# design.net
KiCad netlist of a schematic drawn in EasyEDA Pro
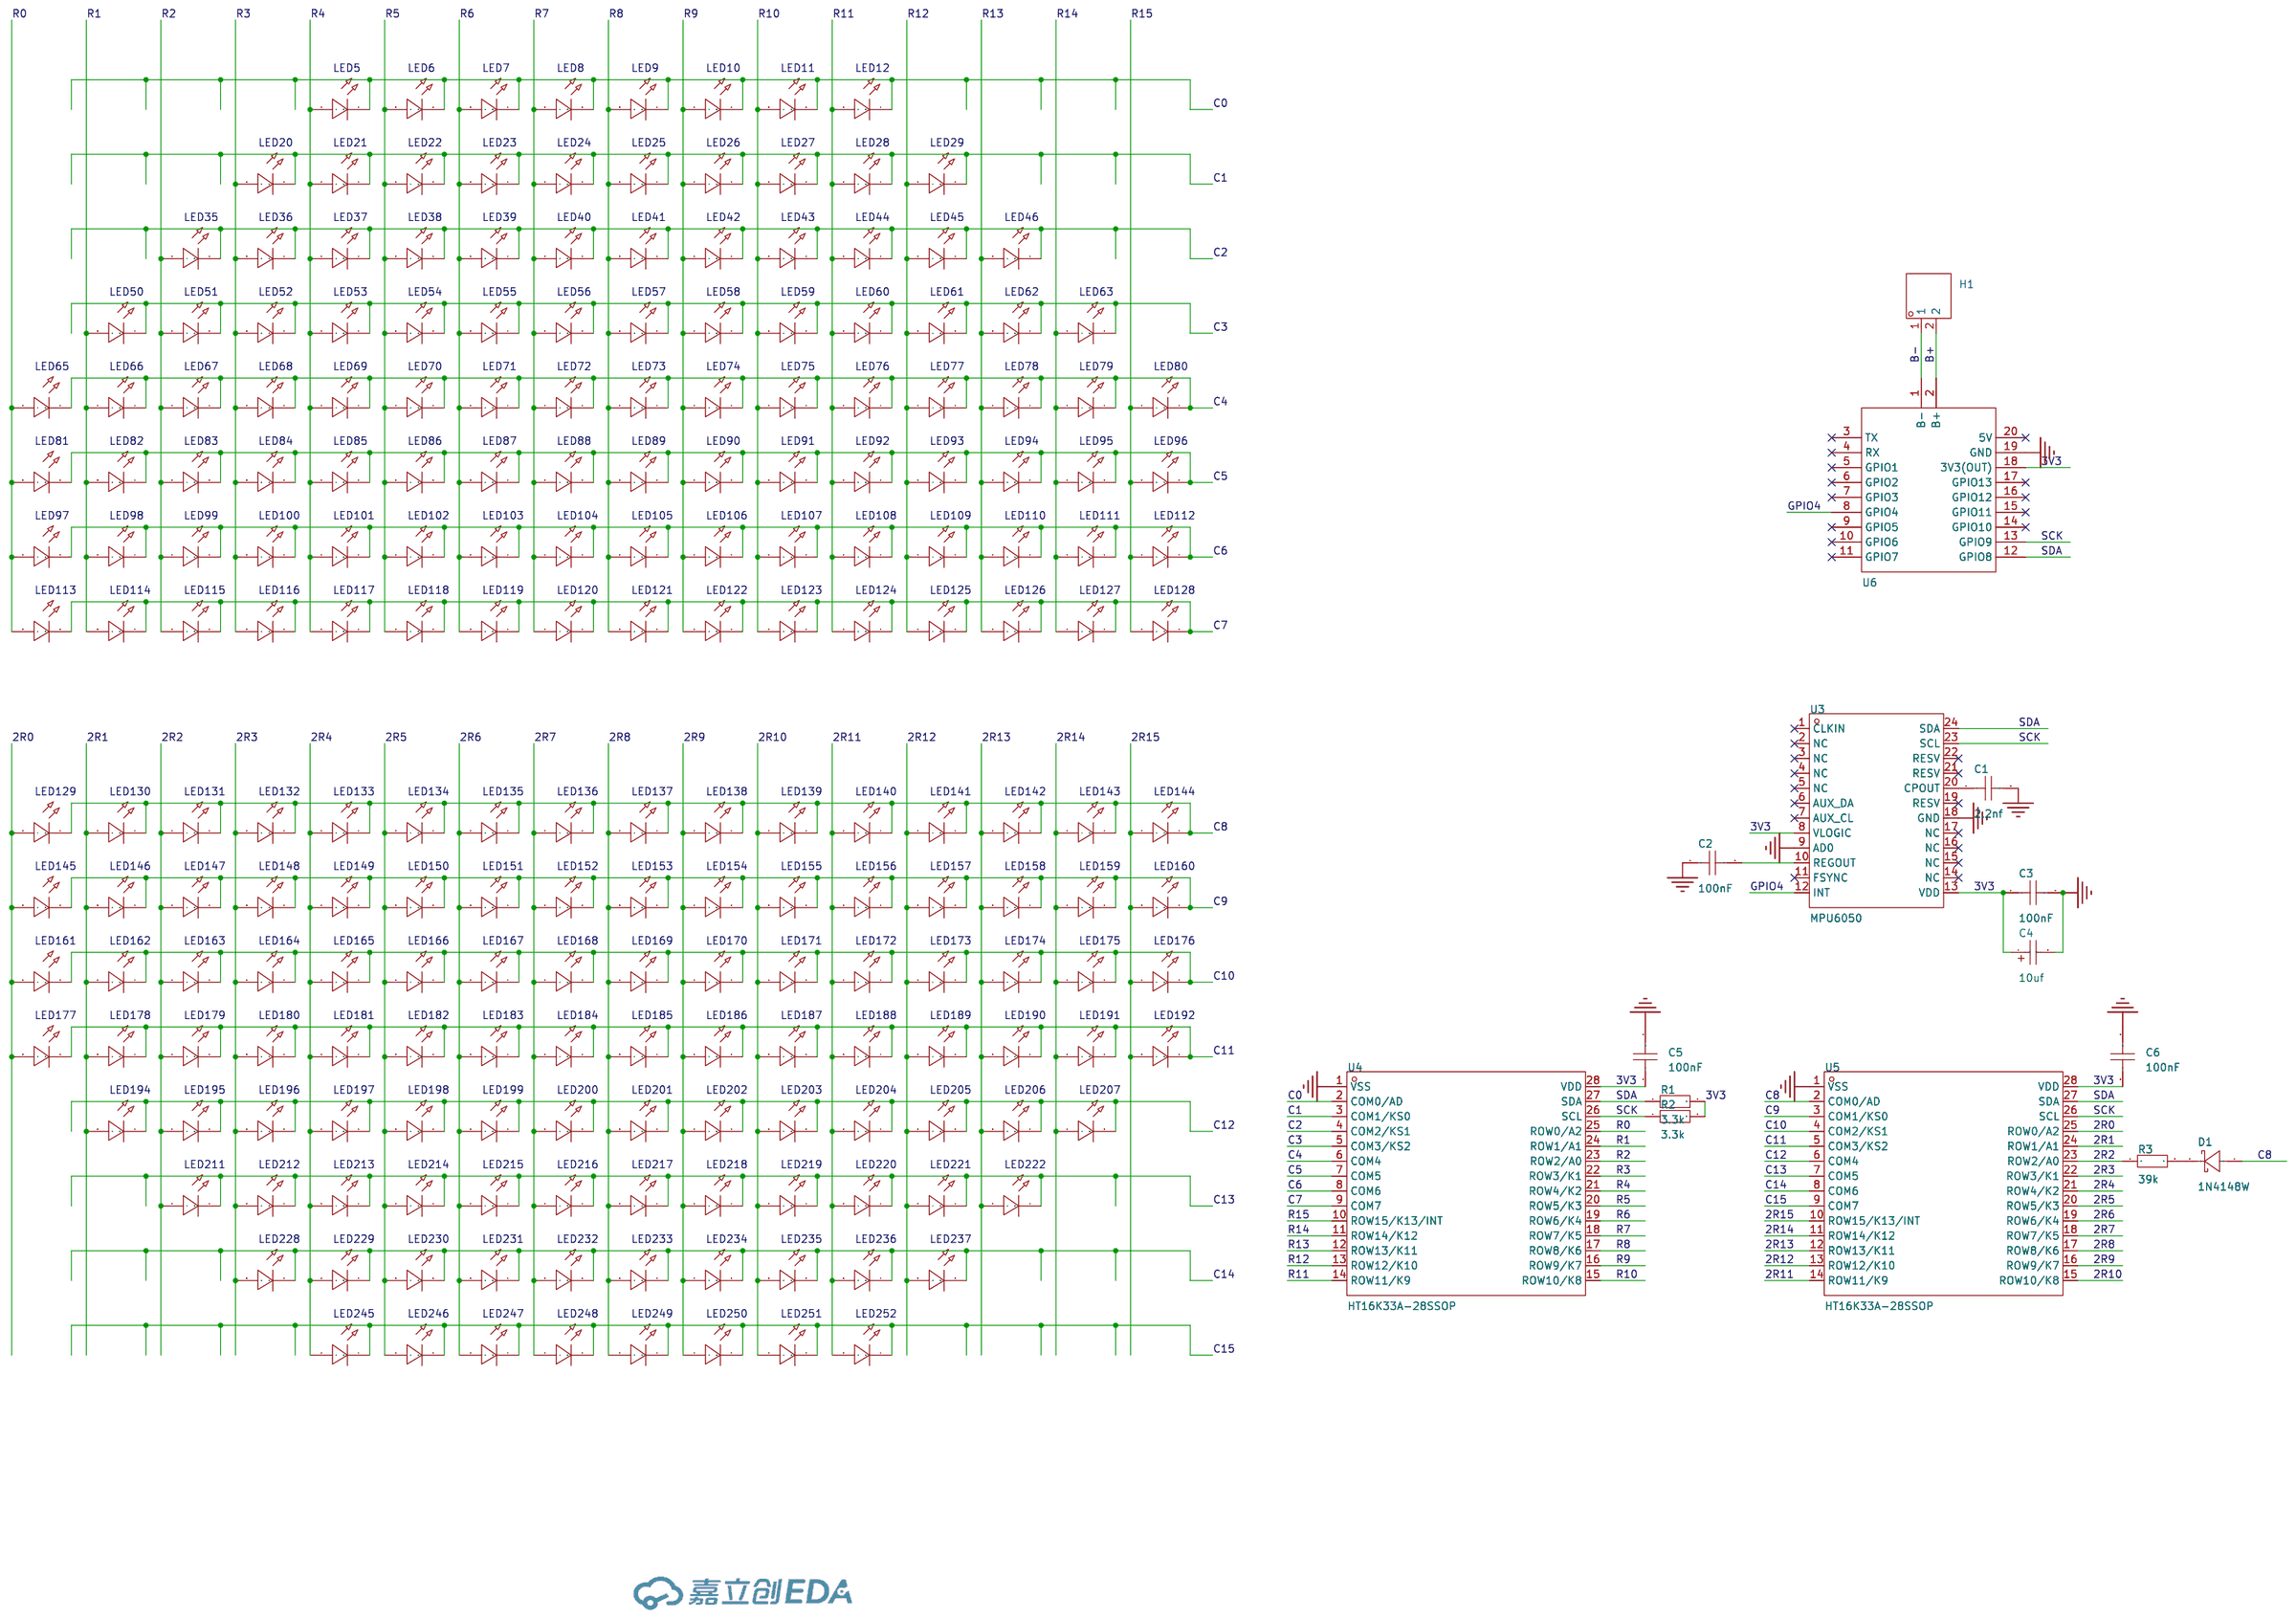
[diagram p0: schematic sheet]

(export (version "E")
  (design (tool "Eeschema 10.0.6"))
  (components
    (comp (ref "C1")
      (value "2.2nf")
      (footprint "easyedapro:C0603")
      (libsource (lib "easyedapro") (part "CapAcitance"))
    )
    (comp (ref "C2")
      (value "100nF")
      (footprint "easyedapro:C0603")
      (libsource (lib "easyedapro") (part "CapAcitance"))
    )
    (comp (ref "C3")
      (value "100nF")
      (footprint "easyedapro:C0603")
      (libsource (lib "easyedapro") (part "CapAcitance"))
    )
    (comp (ref "C4")
      (value "10uf")
      (footprint "easyedapro:CASE-B_3528")
      (description "容值:100uF;精度:±10%;额定电压:6.3V;等效串联电阻(ESR):1.7Ω@100kHz;")
      (fields (field (name "Manufacturer Part") "TAJB107K006RNJ") (field (name "Manufacturer") "Kyocera AVX"))
      (libsource (lib "easyedapro") (part "TAJB107K006RNJ"))
    )
    (comp (ref "C5")
      (value "100nF")
      (footprint "easyedapro:C0603")
      (libsource (lib "easyedapro") (part "CapAcitance"))
    )
    (comp (ref "C6")
      (value "100nF")
      (footprint "easyedapro:C0603")
      (libsource (lib "easyedapro") (part "CapAcitance"))
    )
    (comp (ref "D1")
      (value "1N4148W")
      (footprint "easyedapro:SOD-123_L2.7-W1.6-LS3.7-FD")
      (description "二极管配置:独立式;正向压降(Vf):1.25V@150mA;直流反向耐压(Vr):100V;整流电流:150mA;反向恢复时间(Trr):4ns;")
      (fields (field (name "Manufacturer") "R+O(宏嘉诚)"))
      (libsource (lib "easyedapro") (part "1N4148W_C7420318"))
    )
    (comp (ref "H1")
      (value "~")
      (footprint "easyedapro:HDR-TH_2P-P2.54-V-M-1")
      (libsource (lib "easyedapro") (part "210S-1*2P L=11.6MMGold-plated black"))
    )
    (comp (ref "LED5")
      (value "~")
      (footprint "easyedapro:LED_0402")
      (libsource (lib "easyedapro") (part "LED_G"))
    )
    (comp (ref "LED6")
      (value "~")
      (footprint "easyedapro:LED_0402")
      (libsource (lib "easyedapro") (part "LED_G"))
    )
    (comp (ref "LED7")
      (value "~")
      (footprint "easyedapro:LED_0402")
      (libsource (lib "easyedapro") (part "LED_G"))
    )
    (comp (ref "LED8")
      (value "~")
      (footprint "easyedapro:LED_0402")
      (libsource (lib "easyedapro") (part "LED_G"))
    )
    (comp (ref "LED9")
      (value "~")
      (footprint "easyedapro:LED_0402")
      (libsource (lib "easyedapro") (part "LED_G"))
    )
    (comp (ref "LED10")
      (value "~")
      (footprint "easyedapro:LED_0402")
      (libsource (lib "easyedapro") (part "LED_G"))
    )
    (comp (ref "LED11")
      (value "~")
      (footprint "easyedapro:LED_0402")
      (libsource (lib "easyedapro") (part "LED_G"))
    )
    (comp (ref "LED12")
      (value "~")
      (footprint "easyedapro:LED_0402")
      (libsource (lib "easyedapro") (part "LED_G"))
    )
    (comp (ref "LED20")
      (value "~")
      (footprint "easyedapro:LED_0402")
      (libsource (lib "easyedapro") (part "LED_G"))
    )
    (comp (ref "LED21")
      (value "~")
      (footprint "easyedapro:LED_0402")
      (libsource (lib "easyedapro") (part "LED_G"))
    )
    (comp (ref "LED22")
      (value "~")
      (footprint "easyedapro:LED_0402")
      (libsource (lib "easyedapro") (part "LED_G"))
    )
    (comp (ref "LED23")
      (value "~")
      (footprint "easyedapro:LED_0402")
      (libsource (lib "easyedapro") (part "LED_G"))
    )
    (comp (ref "LED24")
      (value "~")
      (footprint "easyedapro:LED_0402")
      (libsource (lib "easyedapro") (part "LED_G"))
    )
    (comp (ref "LED25")
      (value "~")
      (footprint "easyedapro:LED_0402")
      (libsource (lib "easyedapro") (part "LED_G"))
    )
    (comp (ref "LED26")
      (value "~")
      (footprint "easyedapro:LED_0402")
      (libsource (lib "easyedapro") (part "LED_G"))
    )
    (comp (ref "LED27")
      (value "~")
      (footprint "easyedapro:LED_0402")
      (libsource (lib "easyedapro") (part "LED_G"))
    )
    (comp (ref "LED28")
      (value "~")
      (footprint "easyedapro:LED_0402")
      (libsource (lib "easyedapro") (part "LED_G"))
    )
    (comp (ref "LED29")
      (value "~")
      (footprint "easyedapro:LED_0402")
      (libsource (lib "easyedapro") (part "LED_G"))
    )
    (comp (ref "LED35")
      (value "~")
      (footprint "easyedapro:LED_0402")
      (libsource (lib "easyedapro") (part "LED_G"))
    )
    (comp (ref "LED36")
      (value "~")
      (footprint "easyedapro:LED_0402")
      (libsource (lib "easyedapro") (part "LED_G"))
    )
    (comp (ref "LED37")
      (value "~")
      (footprint "easyedapro:LED_0402")
      (libsource (lib "easyedapro") (part "LED_G"))
    )
    (comp (ref "LED38")
      (value "~")
      (footprint "easyedapro:LED_0402")
      (libsource (lib "easyedapro") (part "LED_G"))
    )
    (comp (ref "LED39")
      (value "~")
      (footprint "easyedapro:LED_0402")
      (libsource (lib "easyedapro") (part "LED_G"))
    )
    (comp (ref "LED40")
      (value "~")
      (footprint "easyedapro:LED_0402")
      (libsource (lib "easyedapro") (part "LED_G"))
    )
    (comp (ref "LED41")
      (value "~")
      (footprint "easyedapro:LED_0402")
      (libsource (lib "easyedapro") (part "LED_G"))
    )
    (comp (ref "LED42")
      (value "~")
      (footprint "easyedapro:LED_0402")
      (libsource (lib "easyedapro") (part "LED_G"))
    )
    (comp (ref "LED43")
      (value "~")
      (footprint "easyedapro:LED_0402")
      (libsource (lib "easyedapro") (part "LED_G"))
    )
    (comp (ref "LED44")
      (value "~")
      (footprint "easyedapro:LED_0402")
      (libsource (lib "easyedapro") (part "LED_G"))
    )
    (comp (ref "LED45")
      (value "~")
      (footprint "easyedapro:LED_0402")
      (libsource (lib "easyedapro") (part "LED_G"))
    )
    (comp (ref "LED46")
      (value "~")
      (footprint "easyedapro:LED_0402")
      (libsource (lib "easyedapro") (part "LED_G"))
    )
    (comp (ref "LED50")
      (value "~")
      (footprint "easyedapro:LED_0402")
      (libsource (lib "easyedapro") (part "LED_G"))
    )
    (comp (ref "LED51")
      (value "~")
      (footprint "easyedapro:LED_0402")
      (libsource (lib "easyedapro") (part "LED_G"))
    )
    (comp (ref "LED52")
      (value "~")
      (footprint "easyedapro:LED_0402")
      (libsource (lib "easyedapro") (part "LED_G"))
    )
    (comp (ref "LED53")
      (value "~")
      (footprint "easyedapro:LED_0402")
      (libsource (lib "easyedapro") (part "LED_G"))
    )
    (comp (ref "LED54")
      (value "~")
      (footprint "easyedapro:LED_0402")
      (libsource (lib "easyedapro") (part "LED_G"))
    )
    (comp (ref "LED55")
      (value "~")
      (footprint "easyedapro:LED_0402")
      (libsource (lib "easyedapro") (part "LED_G"))
    )
    (comp (ref "LED56")
      (value "~")
      (footprint "easyedapro:LED_0402")
      (libsource (lib "easyedapro") (part "LED_G"))
    )
    (comp (ref "LED57")
      (value "~")
      (footprint "easyedapro:LED_0402")
      (libsource (lib "easyedapro") (part "LED_G"))
    )
    (comp (ref "LED58")
      (value "~")
      (footprint "easyedapro:LED_0402")
      (libsource (lib "easyedapro") (part "LED_G"))
    )
    (comp (ref "LED59")
      (value "~")
      (footprint "easyedapro:LED_0402")
      (libsource (lib "easyedapro") (part "LED_G"))
    )
    (comp (ref "LED60")
      (value "~")
      (footprint "easyedapro:LED_0402")
      (libsource (lib "easyedapro") (part "LED_G"))
    )
    (comp (ref "LED61")
      (value "~")
      (footprint "easyedapro:LED_0402")
      (libsource (lib "easyedapro") (part "LED_G"))
    )
    (comp (ref "LED62")
      (value "~")
      (footprint "easyedapro:LED_0402")
      (libsource (lib "easyedapro") (part "LED_G"))
    )
    (comp (ref "LED63")
      (value "~")
      (footprint "easyedapro:LED_0402")
      (libsource (lib "easyedapro") (part "LED_G"))
    )
    (comp (ref "LED65")
      (value "~")
      (footprint "easyedapro:LED_0402")
      (libsource (lib "easyedapro") (part "LED_G"))
    )
    (comp (ref "LED66")
      (value "~")
      (footprint "easyedapro:LED_0402")
      (libsource (lib "easyedapro") (part "LED_G"))
    )
    (comp (ref "LED67")
      (value "~")
      (footprint "easyedapro:LED_0402")
      (libsource (lib "easyedapro") (part "LED_G"))
    )
    (comp (ref "LED68")
      (value "~")
      (footprint "easyedapro:LED_0402")
      (libsource (lib "easyedapro") (part "LED_G"))
    )
    (comp (ref "LED69")
      (value "~")
      (footprint "easyedapro:LED_0402")
      (libsource (lib "easyedapro") (part "LED_G"))
    )
    (comp (ref "LED70")
      (value "~")
      (footprint "easyedapro:LED_0402")
      (libsource (lib "easyedapro") (part "LED_G"))
    )
    (comp (ref "LED71")
      (value "~")
      (footprint "easyedapro:LED_0402")
      (libsource (lib "easyedapro") (part "LED_G"))
    )
    (comp (ref "LED72")
      (value "~")
      (footprint "easyedapro:LED_0402")
      (libsource (lib "easyedapro") (part "LED_G"))
    )
    (comp (ref "LED73")
      (value "~")
      (footprint "easyedapro:LED_0402")
      (libsource (lib "easyedapro") (part "LED_G"))
    )
    (comp (ref "LED74")
      (value "~")
      (footprint "easyedapro:LED_0402")
      (libsource (lib "easyedapro") (part "LED_G"))
    )
    (comp (ref "LED75")
      (value "~")
      (footprint "easyedapro:LED_0402")
      (libsource (lib "easyedapro") (part "LED_G"))
    )
    (comp (ref "LED76")
      (value "~")
      (footprint "easyedapro:LED_0402")
      (libsource (lib "easyedapro") (part "LED_G"))
    )
    (comp (ref "LED77")
      (value "~")
      (footprint "easyedapro:LED_0402")
      (libsource (lib "easyedapro") (part "LED_G"))
    )
    (comp (ref "LED78")
      (value "~")
      (footprint "easyedapro:LED_0402")
      (libsource (lib "easyedapro") (part "LED_G"))
    )
    (comp (ref "LED79")
      (value "~")
      (footprint "easyedapro:LED_0402")
      (libsource (lib "easyedapro") (part "LED_G"))
    )
    (comp (ref "LED80")
      (value "~")
      (footprint "easyedapro:LED_0402")
      (libsource (lib "easyedapro") (part "LED_G"))
    )
    (comp (ref "LED81")
      (value "~")
      (footprint "easyedapro:LED_0402")
      (libsource (lib "easyedapro") (part "LED_G"))
    )
    (comp (ref "LED82")
      (value "~")
      (footprint "easyedapro:LED_0402")
      (libsource (lib "easyedapro") (part "LED_G"))
    )
    (comp (ref "LED83")
      (value "~")
      (footprint "easyedapro:LED_0402")
      (libsource (lib "easyedapro") (part "LED_G"))
    )
    (comp (ref "LED84")
      (value "~")
      (footprint "easyedapro:LED_0402")
      (libsource (lib "easyedapro") (part "LED_G"))
    )
    (comp (ref "LED85")
      (value "~")
      (footprint "easyedapro:LED_0402")
      (libsource (lib "easyedapro") (part "LED_G"))
    )
    (comp (ref "LED86")
      (value "~")
      (footprint "easyedapro:LED_0402")
      (libsource (lib "easyedapro") (part "LED_G"))
    )
    (comp (ref "LED87")
      (value "~")
      (footprint "easyedapro:LED_0402")
      (libsource (lib "easyedapro") (part "LED_G"))
    )
    (comp (ref "LED88")
      (value "~")
      (footprint "easyedapro:LED_0402")
      (libsource (lib "easyedapro") (part "LED_G"))
    )
    (comp (ref "LED89")
      (value "~")
      (footprint "easyedapro:LED_0402")
      (libsource (lib "easyedapro") (part "LED_G"))
    )
    (comp (ref "LED90")
      (value "~")
      (footprint "easyedapro:LED_0402")
      (libsource (lib "easyedapro") (part "LED_G"))
    )
    (comp (ref "LED91")
      (value "~")
      (footprint "easyedapro:LED_0402")
      (libsource (lib "easyedapro") (part "LED_G"))
    )
    (comp (ref "LED92")
      (value "~")
      (footprint "easyedapro:LED_0402")
      (libsource (lib "easyedapro") (part "LED_G"))
    )
    (comp (ref "LED93")
      (value "~")
      (footprint "easyedapro:LED_0402")
      (libsource (lib "easyedapro") (part "LED_G"))
    )
    (comp (ref "LED94")
      (value "~")
      (footprint "easyedapro:LED_0402")
      (libsource (lib "easyedapro") (part "LED_G"))
    )
    (comp (ref "LED95")
      (value "~")
      (footprint "easyedapro:LED_0402")
      (libsource (lib "easyedapro") (part "LED_G"))
    )
    (comp (ref "LED96")
      (value "~")
      (footprint "easyedapro:LED_0402")
      (libsource (lib "easyedapro") (part "LED_G"))
    )
    (comp (ref "LED97")
      (value "~")
      (footprint "easyedapro:LED_0402")
      (libsource (lib "easyedapro") (part "LED_G"))
    )
    (comp (ref "LED98")
      (value "~")
      (footprint "easyedapro:LED_0402")
      (libsource (lib "easyedapro") (part "LED_G"))
    )
    (comp (ref "LED99")
      (value "~")
      (footprint "easyedapro:LED_0402")
      (libsource (lib "easyedapro") (part "LED_G"))
    )
    (comp (ref "LED100")
      (value "~")
      (footprint "easyedapro:LED_0402")
      (libsource (lib "easyedapro") (part "LED_G"))
    )
    (comp (ref "LED101")
      (value "~")
      (footprint "easyedapro:LED_0402")
      (libsource (lib "easyedapro") (part "LED_G"))
    )
    (comp (ref "LED102")
      (value "~")
      (footprint "easyedapro:LED_0402")
      (libsource (lib "easyedapro") (part "LED_G"))
    )
    (comp (ref "LED103")
      (value "~")
      (footprint "easyedapro:LED_0402")
      (libsource (lib "easyedapro") (part "LED_G"))
    )
    (comp (ref "LED104")
      (value "~")
      (footprint "easyedapro:LED_0402")
      (libsource (lib "easyedapro") (part "LED_G"))
    )
    (comp (ref "LED105")
      (value "~")
      (footprint "easyedapro:LED_0402")
      (libsource (lib "easyedapro") (part "LED_G"))
    )
    (comp (ref "LED106")
      (value "~")
      (footprint "easyedapro:LED_0402")
      (libsource (lib "easyedapro") (part "LED_G"))
    )
    (comp (ref "LED107")
      (value "~")
      (footprint "easyedapro:LED_0402")
      (libsource (lib "easyedapro") (part "LED_G"))
    )
    (comp (ref "LED108")
      (value "~")
      (footprint "easyedapro:LED_0402")
      (libsource (lib "easyedapro") (part "LED_G"))
    )
    (comp (ref "LED109")
      (value "~")
      (footprint "easyedapro:LED_0402")
      (libsource (lib "easyedapro") (part "LED_G"))
    )
    (comp (ref "LED110")
      (value "~")
      (footprint "easyedapro:LED_0402")
      (libsource (lib "easyedapro") (part "LED_G"))
    )
    (comp (ref "LED111")
      (value "~")
      (footprint "easyedapro:LED_0402")
      (libsource (lib "easyedapro") (part "LED_G"))
    )
    (comp (ref "LED112")
      (value "~")
      (footprint "easyedapro:LED_0402")
      (libsource (lib "easyedapro") (part "LED_G"))
    )
    (comp (ref "LED113")
      (value "~")
      (footprint "easyedapro:LED_0402")
      (libsource (lib "easyedapro") (part "LED_G"))
    )
    (comp (ref "LED114")
      (value "~")
      (footprint "easyedapro:LED_0402")
      (libsource (lib "easyedapro") (part "LED_G"))
    )
    (comp (ref "LED115")
      (value "~")
      (footprint "easyedapro:LED_0402")
      (libsource (lib "easyedapro") (part "LED_G"))
    )
    (comp (ref "LED116")
      (value "~")
      (footprint "easyedapro:LED_0402")
      (libsource (lib "easyedapro") (part "LED_G"))
    )
    (comp (ref "LED117")
      (value "~")
      (footprint "easyedapro:LED_0402")
      (libsource (lib "easyedapro") (part "LED_G"))
    )
    (comp (ref "LED118")
      (value "~")
      (footprint "easyedapro:LED_0402")
      (libsource (lib "easyedapro") (part "LED_G"))
    )
    (comp (ref "LED119")
      (value "~")
      (footprint "easyedapro:LED_0402")
      (libsource (lib "easyedapro") (part "LED_G"))
    )
    (comp (ref "LED120")
      (value "~")
      (footprint "easyedapro:LED_0402")
      (libsource (lib "easyedapro") (part "LED_G"))
    )
    (comp (ref "LED121")
      (value "~")
      (footprint "easyedapro:LED_0402")
      (libsource (lib "easyedapro") (part "LED_G"))
    )
    (comp (ref "LED122")
      (value "~")
      (footprint "easyedapro:LED_0402")
      (libsource (lib "easyedapro") (part "LED_G"))
    )
    (comp (ref "LED123")
      (value "~")
      (footprint "easyedapro:LED_0402")
      (libsource (lib "easyedapro") (part "LED_G"))
    )
    (comp (ref "LED124")
      (value "~")
      (footprint "easyedapro:LED_0402")
      (libsource (lib "easyedapro") (part "LED_G"))
    )
    (comp (ref "LED125")
      (value "~")
      (footprint "easyedapro:LED_0402")
      (libsource (lib "easyedapro") (part "LED_G"))
    )
    (comp (ref "LED126")
      (value "~")
      (footprint "easyedapro:LED_0402")
      (libsource (lib "easyedapro") (part "LED_G"))
    )
    (comp (ref "LED127")
      (value "~")
      (footprint "easyedapro:LED_0402")
      (libsource (lib "easyedapro") (part "LED_G"))
    )
    (comp (ref "LED128")
      (value "~")
      (footprint "easyedapro:LED_0402")
      (libsource (lib "easyedapro") (part "LED_G"))
    )
    (comp (ref "LED129")
      (value "~")
      (footprint "easyedapro:LED_0402")
      (libsource (lib "easyedapro") (part "LED_G"))
    )
    (comp (ref "LED130")
      (value "~")
      (footprint "easyedapro:LED_0402")
      (libsource (lib "easyedapro") (part "LED_G"))
    )
    (comp (ref "LED131")
      (value "~")
      (footprint "easyedapro:LED_0402")
      (libsource (lib "easyedapro") (part "LED_G"))
    )
    (comp (ref "LED132")
      (value "~")
      (footprint "easyedapro:LED_0402")
      (libsource (lib "easyedapro") (part "LED_G"))
    )
    (comp (ref "LED133")
      (value "~")
      (footprint "easyedapro:LED_0402")
      (libsource (lib "easyedapro") (part "LED_G"))
    )
    (comp (ref "LED134")
      (value "~")
      (footprint "easyedapro:LED_0402")
      (libsource (lib "easyedapro") (part "LED_G"))
    )
    (comp (ref "LED135")
      (value "~")
      (footprint "easyedapro:LED_0402")
      (libsource (lib "easyedapro") (part "LED_G"))
    )
    (comp (ref "LED136")
      (value "~")
      (footprint "easyedapro:LED_0402")
      (libsource (lib "easyedapro") (part "LED_G"))
    )
    (comp (ref "LED137")
      (value "~")
      (footprint "easyedapro:LED_0402")
      (libsource (lib "easyedapro") (part "LED_G"))
    )
    (comp (ref "LED138")
      (value "~")
      (footprint "easyedapro:LED_0402")
      (libsource (lib "easyedapro") (part "LED_G"))
    )
    (comp (ref "LED139")
      (value "~")
      (footprint "easyedapro:LED_0402")
      (libsource (lib "easyedapro") (part "LED_G"))
    )
    (comp (ref "LED140")
      (value "~")
      (footprint "easyedapro:LED_0402")
      (libsource (lib "easyedapro") (part "LED_G"))
    )
    (comp (ref "LED141")
      (value "~")
      (footprint "easyedapro:LED_0402")
      (libsource (lib "easyedapro") (part "LED_G"))
    )
    (comp (ref "LED142")
      (value "~")
      (footprint "easyedapro:LED_0402")
      (libsource (lib "easyedapro") (part "LED_G"))
    )
    (comp (ref "LED143")
      (value "~")
      (footprint "easyedapro:LED_0402")
      (libsource (lib "easyedapro") (part "LED_G"))
    )
    (comp (ref "LED144")
      (value "~")
      (footprint "easyedapro:LED_0402")
      (libsource (lib "easyedapro") (part "LED_G"))
    )
    (comp (ref "LED145")
      (value "~")
      (footprint "easyedapro:LED_0402")
      (libsource (lib "easyedapro") (part "LED_G"))
    )
    (comp (ref "LED146")
      (value "~")
      (footprint "easyedapro:LED_0402")
      (libsource (lib "easyedapro") (part "LED_G"))
    )
    (comp (ref "LED147")
      (value "~")
      (footprint "easyedapro:LED_0402")
      (libsource (lib "easyedapro") (part "LED_G"))
    )
    (comp (ref "LED148")
      (value "~")
      (footprint "easyedapro:LED_0402")
      (libsource (lib "easyedapro") (part "LED_G"))
    )
    (comp (ref "LED149")
      (value "~")
      (footprint "easyedapro:LED_0402")
      (libsource (lib "easyedapro") (part "LED_G"))
    )
    (comp (ref "LED150")
      (value "~")
      (footprint "easyedapro:LED_0402")
      (libsource (lib "easyedapro") (part "LED_G"))
    )
    (comp (ref "LED151")
      (value "~")
      (footprint "easyedapro:LED_0402")
      (libsource (lib "easyedapro") (part "LED_G"))
    )
    (comp (ref "LED152")
      (value "~")
      (footprint "easyedapro:LED_0402")
      (libsource (lib "easyedapro") (part "LED_G"))
    )
    (comp (ref "LED153")
      (value "~")
      (footprint "easyedapro:LED_0402")
      (libsource (lib "easyedapro") (part "LED_G"))
    )
    (comp (ref "LED154")
      (value "~")
      (footprint "easyedapro:LED_0402")
      (libsource (lib "easyedapro") (part "LED_G"))
    )
    (comp (ref "LED155")
      (value "~")
      (footprint "easyedapro:LED_0402")
      (libsource (lib "easyedapro") (part "LED_G"))
    )
    (comp (ref "LED156")
      (value "~")
      (footprint "easyedapro:LED_0402")
      (libsource (lib "easyedapro") (part "LED_G"))
    )
    (comp (ref "LED157")
      (value "~")
      (footprint "easyedapro:LED_0402")
      (libsource (lib "easyedapro") (part "LED_G"))
    )
    (comp (ref "LED158")
      (value "~")
      (footprint "easyedapro:LED_0402")
      (libsource (lib "easyedapro") (part "LED_G"))
    )
    (comp (ref "LED159")
      (value "~")
      (footprint "easyedapro:LED_0402")
      (libsource (lib "easyedapro") (part "LED_G"))
    )
    (comp (ref "LED160")
      (value "~")
      (footprint "easyedapro:LED_0402")
      (libsource (lib "easyedapro") (part "LED_G"))
    )
    (comp (ref "LED161")
      (value "~")
      (footprint "easyedapro:LED_0402")
      (libsource (lib "easyedapro") (part "LED_G"))
    )
    (comp (ref "LED162")
      (value "~")
      (footprint "easyedapro:LED_0402")
      (libsource (lib "easyedapro") (part "LED_G"))
    )
    (comp (ref "LED163")
      (value "~")
      (footprint "easyedapro:LED_0402")
      (libsource (lib "easyedapro") (part "LED_G"))
    )
    (comp (ref "LED164")
      (value "~")
      (footprint "easyedapro:LED_0402")
      (libsource (lib "easyedapro") (part "LED_G"))
    )
    (comp (ref "LED165")
      (value "~")
      (footprint "easyedapro:LED_0402")
      (libsource (lib "easyedapro") (part "LED_G"))
    )
    (comp (ref "LED166")
      (value "~")
      (footprint "easyedapro:LED_0402")
      (libsource (lib "easyedapro") (part "LED_G"))
    )
    (comp (ref "LED167")
      (value "~")
      (footprint "easyedapro:LED_0402")
      (libsource (lib "easyedapro") (part "LED_G"))
    )
    (comp (ref "LED168")
      (value "~")
      (footprint "easyedapro:LED_0402")
      (libsource (lib "easyedapro") (part "LED_G"))
    )
    (comp (ref "LED169")
      (value "~")
      (footprint "easyedapro:LED_0402")
      (libsource (lib "easyedapro") (part "LED_G"))
    )
    (comp (ref "LED170")
      (value "~")
      (footprint "easyedapro:LED_0402")
      (libsource (lib "easyedapro") (part "LED_G"))
    )
    (comp (ref "LED171")
      (value "~")
      (footprint "easyedapro:LED_0402")
      (libsource (lib "easyedapro") (part "LED_G"))
    )
    (comp (ref "LED172")
      (value "~")
      (footprint "easyedapro:LED_0402")
      (libsource (lib "easyedapro") (part "LED_G"))
    )
    (comp (ref "LED173")
      (value "~")
      (footprint "easyedapro:LED_0402")
      (libsource (lib "easyedapro") (part "LED_G"))
    )
    (comp (ref "LED174")
      (value "~")
      (footprint "easyedapro:LED_0402")
      (libsource (lib "easyedapro") (part "LED_G"))
    )
    (comp (ref "LED175")
      (value "~")
      (footprint "easyedapro:LED_0402")
      (libsource (lib "easyedapro") (part "LED_G"))
    )
    (comp (ref "LED176")
      (value "~")
      (footprint "easyedapro:LED_0402")
      (libsource (lib "easyedapro") (part "LED_G"))
    )
    (comp (ref "LED177")
      (value "~")
      (footprint "easyedapro:LED_0402")
      (libsource (lib "easyedapro") (part "LED_G"))
    )
    (comp (ref "LED178")
      (value "~")
      (footprint "easyedapro:LED_0402")
      (libsource (lib "easyedapro") (part "LED_G"))
    )
    (comp (ref "LED179")
      (value "~")
      (footprint "easyedapro:LED_0402")
      (libsource (lib "easyedapro") (part "LED_G"))
    )
    (comp (ref "LED180")
      (value "~")
      (footprint "easyedapro:LED_0402")
      (libsource (lib "easyedapro") (part "LED_G"))
    )
    (comp (ref "LED181")
      (value "~")
      (footprint "easyedapro:LED_0402")
      (libsource (lib "easyedapro") (part "LED_G"))
    )
    (comp (ref "LED182")
      (value "~")
      (footprint "easyedapro:LED_0402")
      (libsource (lib "easyedapro") (part "LED_G"))
    )
    (comp (ref "LED183")
      (value "~")
      (footprint "easyedapro:LED_0402")
      (libsource (lib "easyedapro") (part "LED_G"))
    )
    (comp (ref "LED184")
      (value "~")
      (footprint "easyedapro:LED_0402")
      (libsource (lib "easyedapro") (part "LED_G"))
    )
    (comp (ref "LED185")
      (value "~")
      (footprint "easyedapro:LED_0402")
      (libsource (lib "easyedapro") (part "LED_G"))
    )
    (comp (ref "LED186")
      (value "~")
      (footprint "easyedapro:LED_0402")
      (libsource (lib "easyedapro") (part "LED_G"))
    )
    (comp (ref "LED187")
      (value "~")
      (footprint "easyedapro:LED_0402")
      (libsource (lib "easyedapro") (part "LED_G"))
    )
    (comp (ref "LED188")
      (value "~")
      (footprint "easyedapro:LED_0402")
      (libsource (lib "easyedapro") (part "LED_G"))
    )
    (comp (ref "LED189")
      (value "~")
      (footprint "easyedapro:LED_0402")
      (libsource (lib "easyedapro") (part "LED_G"))
    )
    (comp (ref "LED190")
      (value "~")
      (footprint "easyedapro:LED_0402")
      (libsource (lib "easyedapro") (part "LED_G"))
    )
    (comp (ref "LED191")
      (value "~")
      (footprint "easyedapro:LED_0402")
      (libsource (lib "easyedapro") (part "LED_G"))
    )
    (comp (ref "LED192")
      (value "~")
      (footprint "easyedapro:LED_0402")
      (libsource (lib "easyedapro") (part "LED_G"))
    )
    (comp (ref "LED194")
      (value "~")
      (footprint "easyedapro:LED_0402")
      (libsource (lib "easyedapro") (part "LED_G"))
    )
    (comp (ref "LED195")
      (value "~")
      (footprint "easyedapro:LED_0402")
      (libsource (lib "easyedapro") (part "LED_G"))
    )
    (comp (ref "LED196")
      (value "~")
      (footprint "easyedapro:LED_0402")
      (libsource (lib "easyedapro") (part "LED_G"))
    )
    (comp (ref "LED197")
      (value "~")
      (footprint "easyedapro:LED_0402")
      (libsource (lib "easyedapro") (part "LED_G"))
    )
    (comp (ref "LED198")
      (value "~")
      (footprint "easyedapro:LED_0402")
      (libsource (lib "easyedapro") (part "LED_G"))
    )
    (comp (ref "LED199")
      (value "~")
      (footprint "easyedapro:LED_0402")
      (libsource (lib "easyedapro") (part "LED_G"))
    )
    (comp (ref "LED200")
      (value "~")
      (footprint "easyedapro:LED_0402")
      (libsource (lib "easyedapro") (part "LED_G"))
    )
    (comp (ref "LED201")
      (value "~")
      (footprint "easyedapro:LED_0402")
      (libsource (lib "easyedapro") (part "LED_G"))
    )
    (comp (ref "LED202")
      (value "~")
      (footprint "easyedapro:LED_0402")
      (libsource (lib "easyedapro") (part "LED_G"))
    )
    (comp (ref "LED203")
      (value "~")
      (footprint "easyedapro:LED_0402")
      (libsource (lib "easyedapro") (part "LED_G"))
    )
    (comp (ref "LED204")
      (value "~")
      (footprint "easyedapro:LED_0402")
      (libsource (lib "easyedapro") (part "LED_G"))
    )
    (comp (ref "LED205")
      (value "~")
      (footprint "easyedapro:LED_0402")
      (libsource (lib "easyedapro") (part "LED_G"))
    )
    (comp (ref "LED206")
      (value "~")
      (footprint "easyedapro:LED_0402")
      (libsource (lib "easyedapro") (part "LED_G"))
    )
    (comp (ref "LED207")
      (value "~")
      (footprint "easyedapro:LED_0402")
      (libsource (lib "easyedapro") (part "LED_G"))
    )
    (comp (ref "LED211")
      (value "~")
      (footprint "easyedapro:LED_0402")
      (libsource (lib "easyedapro") (part "LED_G"))
    )
    (comp (ref "LED212")
      (value "~")
      (footprint "easyedapro:LED_0402")
      (libsource (lib "easyedapro") (part "LED_G"))
    )
    (comp (ref "LED213")
      (value "~")
      (footprint "easyedapro:LED_0402")
      (libsource (lib "easyedapro") (part "LED_G"))
    )
    (comp (ref "LED214")
      (value "~")
      (footprint "easyedapro:LED_0402")
      (libsource (lib "easyedapro") (part "LED_G"))
    )
    (comp (ref "LED215")
      (value "~")
      (footprint "easyedapro:LED_0402")
      (libsource (lib "easyedapro") (part "LED_G"))
    )
    (comp (ref "LED216")
      (value "~")
      (footprint "easyedapro:LED_0402")
      (libsource (lib "easyedapro") (part "LED_G"))
    )
    (comp (ref "LED217")
      (value "~")
      (footprint "easyedapro:LED_0402")
      (libsource (lib "easyedapro") (part "LED_G"))
    )
    (comp (ref "LED218")
      (value "~")
      (footprint "easyedapro:LED_0402")
      (libsource (lib "easyedapro") (part "LED_G"))
    )
    (comp (ref "LED219")
      (value "~")
      (footprint "easyedapro:LED_0402")
      (libsource (lib "easyedapro") (part "LED_G"))
    )
    (comp (ref "LED220")
      (value "~")
      (footprint "easyedapro:LED_0402")
      (libsource (lib "easyedapro") (part "LED_G"))
    )
    (comp (ref "LED221")
      (value "~")
      (footprint "easyedapro:LED_0402")
      (libsource (lib "easyedapro") (part "LED_G"))
    )
    (comp (ref "LED222")
      (value "~")
      (footprint "easyedapro:LED_0402")
      (libsource (lib "easyedapro") (part "LED_G"))
    )
    (comp (ref "LED228")
      (value "~")
      (footprint "easyedapro:LED_0402")
      (libsource (lib "easyedapro") (part "LED_G"))
    )
    (comp (ref "LED229")
      (value "~")
      (footprint "easyedapro:LED_0402")
      (libsource (lib "easyedapro") (part "LED_G"))
    )
    (comp (ref "LED230")
      (value "~")
      (footprint "easyedapro:LED_0402")
      (libsource (lib "easyedapro") (part "LED_G"))
    )
    (comp (ref "LED231")
      (value "~")
      (footprint "easyedapro:LED_0402")
      (libsource (lib "easyedapro") (part "LED_G"))
    )
    (comp (ref "LED232")
      (value "~")
      (footprint "easyedapro:LED_0402")
      (libsource (lib "easyedapro") (part "LED_G"))
    )
    (comp (ref "LED233")
      (value "~")
      (footprint "easyedapro:LED_0402")
      (libsource (lib "easyedapro") (part "LED_G"))
    )
    (comp (ref "LED234")
      (value "~")
      (footprint "easyedapro:LED_0402")
      (libsource (lib "easyedapro") (part "LED_G"))
    )
    (comp (ref "LED235")
      (value "~")
      (footprint "easyedapro:LED_0402")
      (libsource (lib "easyedapro") (part "LED_G"))
    )
    (comp (ref "LED236")
      (value "~")
      (footprint "easyedapro:LED_0402")
      (libsource (lib "easyedapro") (part "LED_G"))
    )
    (comp (ref "LED237")
      (value "~")
      (footprint "easyedapro:LED_0402")
      (libsource (lib "easyedapro") (part "LED_G"))
    )
    (comp (ref "LED245")
      (value "~")
      (footprint "easyedapro:LED_0402")
      (libsource (lib "easyedapro") (part "LED_G"))
    )
    (comp (ref "LED246")
      (value "~")
      (footprint "easyedapro:LED_0402")
      (libsource (lib "easyedapro") (part "LED_G"))
    )
    (comp (ref "LED247")
      (value "~")
      (footprint "easyedapro:LED_0402")
      (libsource (lib "easyedapro") (part "LED_G"))
    )
    (comp (ref "LED248")
      (value "~")
      (footprint "easyedapro:LED_0402")
      (libsource (lib "easyedapro") (part "LED_G"))
    )
    (comp (ref "LED249")
      (value "~")
      (footprint "easyedapro:LED_0402")
      (libsource (lib "easyedapro") (part "LED_G"))
    )
    (comp (ref "LED250")
      (value "~")
      (footprint "easyedapro:LED_0402")
      (libsource (lib "easyedapro") (part "LED_G"))
    )
    (comp (ref "LED251")
      (value "~")
      (footprint "easyedapro:LED_0402")
      (libsource (lib "easyedapro") (part "LED_G"))
    )
    (comp (ref "LED252")
      (value "~")
      (footprint "easyedapro:LED_0402")
      (libsource (lib "easyedapro") (part "LED_G"))
    )
    (comp (ref "R1") (value "3.3k") (footprint "easyedapro:R0402") (libsource (lib "easyedapro") (part "电阻")))
    (comp (ref "R2") (value "3.3k") (footprint "easyedapro:R0402") (libsource (lib "easyedapro") (part "电阻")))
    (comp (ref "R3") (value "39k") (footprint "easyedapro:R0402") (libsource (lib "easyedapro") (part "电阻")))
    (comp (ref "U3")
      (value "MPU6050")
      (footprint "easyedapro:QFN-24_L4.0-W4.0-P0.50-BL")
      (libsource (lib "easyedapro") (part "MPU6050_C9900042518"))
    )
    (comp (ref "U4")
      (value "HT16K33A-28SSOP")
      (footprint "easyedapro:SSOP-28_L9.9-W3.9-P0.64-LS6.0-BL")
      (fields (field (name "Manufacturer") "HOLTEK(合泰/盛群)"))
      (libsource (lib "easyedapro") (part "HT16K33A-28SSOP"))
    )
    (comp (ref "U5")
      (value "HT16K33A-28SSOP")
      (footprint "easyedapro:SSOP-28_L9.9-W3.9-P0.64-LS6.0-BL")
      (fields (field (name "Manufacturer") "HOLTEK(合泰/盛群)"))
      (libsource (lib "easyedapro") (part "HT16K33A-28SSOP"))
    )
    (comp (ref "U6")
      (value "~")
      (footprint "easyedapro:esp32 suoermini s3")
      (libsource (lib "easyedapro") (part "esp32 supermini s3"))
    )
  )
  (nets
    (net (code "1") (name "/2R0") (class "Default")
      (node (ref "LED129") (pin "2") (pinfunction "A_2") (pintype "input"))
      (node (ref "LED145") (pin "2") (pinfunction "A_2") (pintype "input"))
      (node (ref "LED161") (pin "2") (pinfunction "A_2") (pintype "input"))
      (node (ref "LED177") (pin "2") (pinfunction "A_2") (pintype "input"))
      (node (ref "U5") (pin "25") (pinfunction "ROW0/A2_25") (pintype "unspecified"))
    )
    (net (code "2") (name "/2R1") (class "Default")
      (node (ref "LED130") (pin "2") (pinfunction "A_2") (pintype "input"))
      (node (ref "LED146") (pin "2") (pinfunction "A_2") (pintype "input"))
      (node (ref "LED162") (pin "2") (pinfunction "A_2") (pintype "input"))
      (node (ref "LED178") (pin "2") (pinfunction "A_2") (pintype "input"))
      (node (ref "LED194") (pin "2") (pinfunction "A_2") (pintype "input"))
      (node (ref "U5") (pin "24") (pinfunction "ROW1/A1_24") (pintype "unspecified"))
    )
    (net (code "3") (name "/2R2") (class "Default")
      (node (ref "LED131") (pin "2") (pinfunction "A_2") (pintype "input"))
      (node (ref "LED147") (pin "2") (pinfunction "A_2") (pintype "input"))
      (node (ref "LED163") (pin "2") (pinfunction "A_2") (pintype "input"))
      (node (ref "LED179") (pin "2") (pinfunction "A_2") (pintype "input"))
      (node (ref "LED195") (pin "2") (pinfunction "A_2") (pintype "input"))
      (node (ref "LED211") (pin "2") (pinfunction "A_2") (pintype "input"))
      (node (ref "R3") (pin "1") (pinfunction "1_1") (pintype "input"))
      (node (ref "U5") (pin "23") (pinfunction "ROW2/A0_23") (pintype "unspecified"))
    )
    (net (code "4") (name "/2R3") (class "Default")
      (node (ref "LED132") (pin "2") (pinfunction "A_2") (pintype "input"))
      (node (ref "LED148") (pin "2") (pinfunction "A_2") (pintype "input"))
      (node (ref "LED164") (pin "2") (pinfunction "A_2") (pintype "input"))
      (node (ref "LED180") (pin "2") (pinfunction "A_2") (pintype "input"))
      (node (ref "LED196") (pin "2") (pinfunction "A_2") (pintype "input"))
      (node (ref "LED212") (pin "2") (pinfunction "A_2") (pintype "input"))
      (node (ref "LED228") (pin "2") (pinfunction "A_2") (pintype "input"))
      (node (ref "U5") (pin "22") (pinfunction "ROW3/K1_22") (pintype "unspecified"))
    )
    (net (code "5") (name "/2R4") (class "Default")
      (node (ref "LED133") (pin "2") (pinfunction "A_2") (pintype "input"))
      (node (ref "LED149") (pin "2") (pinfunction "A_2") (pintype "input"))
      (node (ref "LED165") (pin "2") (pinfunction "A_2") (pintype "input"))
      (node (ref "LED181") (pin "2") (pinfunction "A_2") (pintype "input"))
      (node (ref "LED197") (pin "2") (pinfunction "A_2") (pintype "input"))
      (node (ref "LED213") (pin "2") (pinfunction "A_2") (pintype "input"))
      (node (ref "LED229") (pin "2") (pinfunction "A_2") (pintype "input"))
      (node (ref "LED245") (pin "2") (pinfunction "A_2") (pintype "input"))
      (node (ref "U5") (pin "21") (pinfunction "ROW4/K2_21") (pintype "unspecified"))
    )
    (net (code "6") (name "/2R5") (class "Default")
      (node (ref "LED134") (pin "2") (pinfunction "A_2") (pintype "input"))
      (node (ref "LED150") (pin "2") (pinfunction "A_2") (pintype "input"))
      (node (ref "LED166") (pin "2") (pinfunction "A_2") (pintype "input"))
      (node (ref "LED182") (pin "2") (pinfunction "A_2") (pintype "input"))
      (node (ref "LED198") (pin "2") (pinfunction "A_2") (pintype "input"))
      (node (ref "LED214") (pin "2") (pinfunction "A_2") (pintype "input"))
      (node (ref "LED230") (pin "2") (pinfunction "A_2") (pintype "input"))
      (node (ref "LED246") (pin "2") (pinfunction "A_2") (pintype "input"))
      (node (ref "U5") (pin "20") (pinfunction "ROW5/K3_20") (pintype "unspecified"))
    )
    (net (code "7") (name "/2R6") (class "Default")
      (node (ref "LED135") (pin "2") (pinfunction "A_2") (pintype "input"))
      (node (ref "LED151") (pin "2") (pinfunction "A_2") (pintype "input"))
      (node (ref "LED167") (pin "2") (pinfunction "A_2") (pintype "input"))
      (node (ref "LED183") (pin "2") (pinfunction "A_2") (pintype "input"))
      (node (ref "LED199") (pin "2") (pinfunction "A_2") (pintype "input"))
      (node (ref "LED215") (pin "2") (pinfunction "A_2") (pintype "input"))
      (node (ref "LED231") (pin "2") (pinfunction "A_2") (pintype "input"))
      (node (ref "LED247") (pin "2") (pinfunction "A_2") (pintype "input"))
      (node (ref "U5") (pin "19") (pinfunction "ROW6/K4_19") (pintype "unspecified"))
    )
    (net (code "8") (name "/2R7") (class "Default")
      (node (ref "LED136") (pin "2") (pinfunction "A_2") (pintype "input"))
      (node (ref "LED152") (pin "2") (pinfunction "A_2") (pintype "input"))
      (node (ref "LED168") (pin "2") (pinfunction "A_2") (pintype "input"))
      (node (ref "LED184") (pin "2") (pinfunction "A_2") (pintype "input"))
      (node (ref "LED200") (pin "2") (pinfunction "A_2") (pintype "input"))
      (node (ref "LED216") (pin "2") (pinfunction "A_2") (pintype "input"))
      (node (ref "LED232") (pin "2") (pinfunction "A_2") (pintype "input"))
      (node (ref "LED248") (pin "2") (pinfunction "A_2") (pintype "input"))
      (node (ref "U5") (pin "18") (pinfunction "ROW7/K5_18") (pintype "unspecified"))
    )
    (net (code "9") (name "/2R8") (class "Default")
      (node (ref "LED137") (pin "2") (pinfunction "A_2") (pintype "input"))
      (node (ref "LED153") (pin "2") (pinfunction "A_2") (pintype "input"))
      (node (ref "LED169") (pin "2") (pinfunction "A_2") (pintype "input"))
      (node (ref "LED185") (pin "2") (pinfunction "A_2") (pintype "input"))
      (node (ref "LED201") (pin "2") (pinfunction "A_2") (pintype "input"))
      (node (ref "LED217") (pin "2") (pinfunction "A_2") (pintype "input"))
      (node (ref "LED233") (pin "2") (pinfunction "A_2") (pintype "input"))
      (node (ref "LED249") (pin "2") (pinfunction "A_2") (pintype "input"))
      (node (ref "U5") (pin "17") (pinfunction "ROW8/K6_17") (pintype "unspecified"))
    )
    (net (code "10") (name "/2R9") (class "Default")
      (node (ref "LED138") (pin "2") (pinfunction "A_2") (pintype "input"))
      (node (ref "LED154") (pin "2") (pinfunction "A_2") (pintype "input"))
      (node (ref "LED170") (pin "2") (pinfunction "A_2") (pintype "input"))
      (node (ref "LED186") (pin "2") (pinfunction "A_2") (pintype "input"))
      (node (ref "LED202") (pin "2") (pinfunction "A_2") (pintype "input"))
      (node (ref "LED218") (pin "2") (pinfunction "A_2") (pintype "input"))
      (node (ref "LED234") (pin "2") (pinfunction "A_2") (pintype "input"))
      (node (ref "LED250") (pin "2") (pinfunction "A_2") (pintype "input"))
      (node (ref "U5") (pin "16") (pinfunction "ROW9/K7_16") (pintype "unspecified"))
    )
    (net (code "11") (name "/2R10") (class "Default")
      (node (ref "LED139") (pin "2") (pinfunction "A_2") (pintype "input"))
      (node (ref "LED155") (pin "2") (pinfunction "A_2") (pintype "input"))
      (node (ref "LED171") (pin "2") (pinfunction "A_2") (pintype "input"))
      (node (ref "LED187") (pin "2") (pinfunction "A_2") (pintype "input"))
      (node (ref "LED203") (pin "2") (pinfunction "A_2") (pintype "input"))
      (node (ref "LED219") (pin "2") (pinfunction "A_2") (pintype "input"))
      (node (ref "LED235") (pin "2") (pinfunction "A_2") (pintype "input"))
      (node (ref "LED251") (pin "2") (pinfunction "A_2") (pintype "input"))
      (node (ref "U5") (pin "15") (pinfunction "ROW10/K8_15") (pintype "unspecified"))
    )
    (net (code "12") (name "/2R11") (class "Default")
      (node (ref "LED140") (pin "2") (pinfunction "A_2") (pintype "input"))
      (node (ref "LED156") (pin "2") (pinfunction "A_2") (pintype "input"))
      (node (ref "LED172") (pin "2") (pinfunction "A_2") (pintype "input"))
      (node (ref "LED188") (pin "2") (pinfunction "A_2") (pintype "input"))
      (node (ref "LED204") (pin "2") (pinfunction "A_2") (pintype "input"))
      (node (ref "LED220") (pin "2") (pinfunction "A_2") (pintype "input"))
      (node (ref "LED236") (pin "2") (pinfunction "A_2") (pintype "input"))
      (node (ref "LED252") (pin "2") (pinfunction "A_2") (pintype "input"))
      (node (ref "U5") (pin "14") (pinfunction "ROW11/K9_14") (pintype "unspecified"))
    )
    (net (code "13") (name "/2R12") (class "Default")
      (node (ref "LED141") (pin "2") (pinfunction "A_2") (pintype "input"))
      (node (ref "LED157") (pin "2") (pinfunction "A_2") (pintype "input"))
      (node (ref "LED173") (pin "2") (pinfunction "A_2") (pintype "input"))
      (node (ref "LED189") (pin "2") (pinfunction "A_2") (pintype "input"))
      (node (ref "LED205") (pin "2") (pinfunction "A_2") (pintype "input"))
      (node (ref "LED221") (pin "2") (pinfunction "A_2") (pintype "input"))
      (node (ref "LED237") (pin "2") (pinfunction "A_2") (pintype "input"))
      (node (ref "U5") (pin "13") (pinfunction "ROW12/K10_13") (pintype "unspecified"))
    )
    (net (code "14") (name "/2R13") (class "Default")
      (node (ref "LED142") (pin "2") (pinfunction "A_2") (pintype "input"))
      (node (ref "LED158") (pin "2") (pinfunction "A_2") (pintype "input"))
      (node (ref "LED174") (pin "2") (pinfunction "A_2") (pintype "input"))
      (node (ref "LED190") (pin "2") (pinfunction "A_2") (pintype "input"))
      (node (ref "LED206") (pin "2") (pinfunction "A_2") (pintype "input"))
      (node (ref "LED222") (pin "2") (pinfunction "A_2") (pintype "input"))
      (node (ref "U5") (pin "12") (pinfunction "ROW13/K11_12") (pintype "unspecified"))
    )
    (net (code "15") (name "/2R14") (class "Default")
      (node (ref "LED143") (pin "2") (pinfunction "A_2") (pintype "input"))
      (node (ref "LED159") (pin "2") (pinfunction "A_2") (pintype "input"))
      (node (ref "LED175") (pin "2") (pinfunction "A_2") (pintype "input"))
      (node (ref "LED191") (pin "2") (pinfunction "A_2") (pintype "input"))
      (node (ref "LED207") (pin "2") (pinfunction "A_2") (pintype "input"))
      (node (ref "U5") (pin "11") (pinfunction "ROW14/K12_11") (pintype "unspecified"))
    )
    (net (code "16") (name "/2R15") (class "Default")
      (node (ref "LED144") (pin "2") (pinfunction "A_2") (pintype "input"))
      (node (ref "LED160") (pin "2") (pinfunction "A_2") (pintype "input"))
      (node (ref "LED176") (pin "2") (pinfunction "A_2") (pintype "input"))
      (node (ref "LED192") (pin "2") (pinfunction "A_2") (pintype "input"))
      (node (ref "U5") (pin "10") (pinfunction "ROW15/K13/INT_10") (pintype "unspecified"))
    )
    (net (code "17") (name "/3V3") (class "Default")
      (node (ref "C3") (pin "1") (pinfunction "1_1") (pintype "input"))
      (node (ref "C4") (pin "1") (pinfunction "1_1") (pintype "input"))
      (node (ref "C5") (pin "1") (pinfunction "1_1") (pintype "input"))
      (node (ref "C6") (pin "1") (pinfunction "1_1") (pintype "input"))
      (node (ref "R1") (pin "2") (pinfunction "2_2") (pintype "input"))
      (node (ref "R2") (pin "2") (pinfunction "2_2") (pintype "input"))
      (node (ref "U3") (pin "13") (pinfunction "VDD_13") (pintype "unspecified"))
      (node (ref "U3") (pin "8") (pinfunction "VLOGIC_8") (pintype "unspecified"))
      (node (ref "U4") (pin "28") (pinfunction "VDD_28") (pintype "unspecified"))
      (node (ref "U5") (pin "28") (pinfunction "VDD_28") (pintype "unspecified"))
      (node (ref "U6") (pin "18") (pinfunction "3V3(OUT)_18") (pintype "input"))
    )
    (net (code "18") (name "/B+") (class "Default")
      (node (ref "H1") (pin "2") (pinfunction "2_2") (pintype "unspecified"))
      (node (ref "U6") (pin "2") (pinfunction "B+_2") (pintype "input"))
    )
    (net (code "19") (name "/B-") (class "Default")
      (node (ref "H1") (pin "1") (pinfunction "1_1") (pintype "unspecified"))
      (node (ref "U6") (pin "1") (pinfunction "B-_1") (pintype "input"))
    )
    (net (code "20") (name "/C0") (class "Default")
      (node (ref "LED10") (pin "1") (pinfunction "C_1") (pintype "input"))
      (node (ref "LED11") (pin "1") (pinfunction "C_1") (pintype "input"))
      (node (ref "LED12") (pin "1") (pinfunction "C_1") (pintype "input"))
      (node (ref "LED5") (pin "1") (pinfunction "C_1") (pintype "input"))
      (node (ref "LED6") (pin "1") (pinfunction "C_1") (pintype "input"))
      (node (ref "LED7") (pin "1") (pinfunction "C_1") (pintype "input"))
      (node (ref "LED8") (pin "1") (pinfunction "C_1") (pintype "input"))
      (node (ref "LED9") (pin "1") (pinfunction "C_1") (pintype "input"))
      (node (ref "U4") (pin "2") (pinfunction "COM0/AD_2") (pintype "unspecified"))
    )
    (net (code "21") (name "/C1") (class "Default")
      (node (ref "LED20") (pin "1") (pinfunction "C_1") (pintype "input"))
      (node (ref "LED21") (pin "1") (pinfunction "C_1") (pintype "input"))
      (node (ref "LED22") (pin "1") (pinfunction "C_1") (pintype "input"))
      (node (ref "LED23") (pin "1") (pinfunction "C_1") (pintype "input"))
      (node (ref "LED24") (pin "1") (pinfunction "C_1") (pintype "input"))
      (node (ref "LED25") (pin "1") (pinfunction "C_1") (pintype "input"))
      (node (ref "LED26") (pin "1") (pinfunction "C_1") (pintype "input"))
      (node (ref "LED27") (pin "1") (pinfunction "C_1") (pintype "input"))
      (node (ref "LED28") (pin "1") (pinfunction "C_1") (pintype "input"))
      (node (ref "LED29") (pin "1") (pinfunction "C_1") (pintype "input"))
      (node (ref "U4") (pin "3") (pinfunction "COM1/KS0_3") (pintype "unspecified"))
    )
    (net (code "22") (name "/C2") (class "Default")
      (node (ref "LED35") (pin "1") (pinfunction "C_1") (pintype "input"))
      (node (ref "LED36") (pin "1") (pinfunction "C_1") (pintype "input"))
      (node (ref "LED37") (pin "1") (pinfunction "C_1") (pintype "input"))
      (node (ref "LED38") (pin "1") (pinfunction "C_1") (pintype "input"))
      (node (ref "LED39") (pin "1") (pinfunction "C_1") (pintype "input"))
      (node (ref "LED40") (pin "1") (pinfunction "C_1") (pintype "input"))
      (node (ref "LED41") (pin "1") (pinfunction "C_1") (pintype "input"))
      (node (ref "LED42") (pin "1") (pinfunction "C_1") (pintype "input"))
      (node (ref "LED43") (pin "1") (pinfunction "C_1") (pintype "input"))
      (node (ref "LED44") (pin "1") (pinfunction "C_1") (pintype "input"))
      (node (ref "LED45") (pin "1") (pinfunction "C_1") (pintype "input"))
      (node (ref "LED46") (pin "1") (pinfunction "C_1") (pintype "input"))
      (node (ref "U4") (pin "4") (pinfunction "COM2/KS1_4") (pintype "unspecified"))
    )
    (net (code "23") (name "/C3") (class "Default")
      (node (ref "LED50") (pin "1") (pinfunction "C_1") (pintype "input"))
      (node (ref "LED51") (pin "1") (pinfunction "C_1") (pintype "input"))
      (node (ref "LED52") (pin "1") (pinfunction "C_1") (pintype "input"))
      (node (ref "LED53") (pin "1") (pinfunction "C_1") (pintype "input"))
      (node (ref "LED54") (pin "1") (pinfunction "C_1") (pintype "input"))
      (node (ref "LED55") (pin "1") (pinfunction "C_1") (pintype "input"))
      (node (ref "LED56") (pin "1") (pinfunction "C_1") (pintype "input"))
      (node (ref "LED57") (pin "1") (pinfunction "C_1") (pintype "input"))
      (node (ref "LED58") (pin "1") (pinfunction "C_1") (pintype "input"))
      (node (ref "LED59") (pin "1") (pinfunction "C_1") (pintype "input"))
      (node (ref "LED60") (pin "1") (pinfunction "C_1") (pintype "input"))
      (node (ref "LED61") (pin "1") (pinfunction "C_1") (pintype "input"))
      (node (ref "LED62") (pin "1") (pinfunction "C_1") (pintype "input"))
      (node (ref "LED63") (pin "1") (pinfunction "C_1") (pintype "input"))
      (node (ref "U4") (pin "5") (pinfunction "COM3/KS2_5") (pintype "unspecified"))
    )
    (net (code "24") (name "/C4") (class "Default")
      (node (ref "LED65") (pin "1") (pinfunction "C_1") (pintype "input"))
      (node (ref "LED66") (pin "1") (pinfunction "C_1") (pintype "input"))
      (node (ref "LED67") (pin "1") (pinfunction "C_1") (pintype "input"))
      (node (ref "LED68") (pin "1") (pinfunction "C_1") (pintype "input"))
      (node (ref "LED69") (pin "1") (pinfunction "C_1") (pintype "input"))
      (node (ref "LED70") (pin "1") (pinfunction "C_1") (pintype "input"))
      (node (ref "LED71") (pin "1") (pinfunction "C_1") (pintype "input"))
      (node (ref "LED72") (pin "1") (pinfunction "C_1") (pintype "input"))
      (node (ref "LED73") (pin "1") (pinfunction "C_1") (pintype "input"))
      (node (ref "LED74") (pin "1") (pinfunction "C_1") (pintype "input"))
      (node (ref "LED75") (pin "1") (pinfunction "C_1") (pintype "input"))
      (node (ref "LED76") (pin "1") (pinfunction "C_1") (pintype "input"))
      (node (ref "LED77") (pin "1") (pinfunction "C_1") (pintype "input"))
      (node (ref "LED78") (pin "1") (pinfunction "C_1") (pintype "input"))
      (node (ref "LED79") (pin "1") (pinfunction "C_1") (pintype "input"))
      (node (ref "LED80") (pin "1") (pinfunction "C_1") (pintype "input"))
      (node (ref "U4") (pin "6") (pinfunction "COM4_6") (pintype "unspecified"))
    )
    (net (code "25") (name "/C5") (class "Default")
      (node (ref "LED81") (pin "1") (pinfunction "C_1") (pintype "input"))
      (node (ref "LED82") (pin "1") (pinfunction "C_1") (pintype "input"))
      (node (ref "LED83") (pin "1") (pinfunction "C_1") (pintype "input"))
      (node (ref "LED84") (pin "1") (pinfunction "C_1") (pintype "input"))
      (node (ref "LED85") (pin "1") (pinfunction "C_1") (pintype "input"))
      (node (ref "LED86") (pin "1") (pinfunction "C_1") (pintype "input"))
      (node (ref "LED87") (pin "1") (pinfunction "C_1") (pintype "input"))
      (node (ref "LED88") (pin "1") (pinfunction "C_1") (pintype "input"))
      (node (ref "LED89") (pin "1") (pinfunction "C_1") (pintype "input"))
      (node (ref "LED90") (pin "1") (pinfunction "C_1") (pintype "input"))
      (node (ref "LED91") (pin "1") (pinfunction "C_1") (pintype "input"))
      (node (ref "LED92") (pin "1") (pinfunction "C_1") (pintype "input"))
      (node (ref "LED93") (pin "1") (pinfunction "C_1") (pintype "input"))
      (node (ref "LED94") (pin "1") (pinfunction "C_1") (pintype "input"))
      (node (ref "LED95") (pin "1") (pinfunction "C_1") (pintype "input"))
      (node (ref "LED96") (pin "1") (pinfunction "C_1") (pintype "input"))
      (node (ref "U4") (pin "7") (pinfunction "COM5_7") (pintype "unspecified"))
    )
    (net (code "26") (name "/C6") (class "Default")
      (node (ref "LED100") (pin "1") (pinfunction "C_1") (pintype "input"))
      (node (ref "LED101") (pin "1") (pinfunction "C_1") (pintype "input"))
      (node (ref "LED102") (pin "1") (pinfunction "C_1") (pintype "input"))
      (node (ref "LED103") (pin "1") (pinfunction "C_1") (pintype "input"))
      (node (ref "LED104") (pin "1") (pinfunction "C_1") (pintype "input"))
      (node (ref "LED105") (pin "1") (pinfunction "C_1") (pintype "input"))
      (node (ref "LED106") (pin "1") (pinfunction "C_1") (pintype "input"))
      (node (ref "LED107") (pin "1") (pinfunction "C_1") (pintype "input"))
      (node (ref "LED108") (pin "1") (pinfunction "C_1") (pintype "input"))
      (node (ref "LED109") (pin "1") (pinfunction "C_1") (pintype "input"))
      (node (ref "LED110") (pin "1") (pinfunction "C_1") (pintype "input"))
      (node (ref "LED111") (pin "1") (pinfunction "C_1") (pintype "input"))
      (node (ref "LED112") (pin "1") (pinfunction "C_1") (pintype "input"))
      (node (ref "LED97") (pin "1") (pinfunction "C_1") (pintype "input"))
      (node (ref "LED98") (pin "1") (pinfunction "C_1") (pintype "input"))
      (node (ref "LED99") (pin "1") (pinfunction "C_1") (pintype "input"))
      (node (ref "U4") (pin "8") (pinfunction "COM6_8") (pintype "unspecified"))
    )
    (net (code "27") (name "/C7") (class "Default")
      (node (ref "LED113") (pin "1") (pinfunction "C_1") (pintype "input"))
      (node (ref "LED114") (pin "1") (pinfunction "C_1") (pintype "input"))
      (node (ref "LED115") (pin "1") (pinfunction "C_1") (pintype "input"))
      (node (ref "LED116") (pin "1") (pinfunction "C_1") (pintype "input"))
      (node (ref "LED117") (pin "1") (pinfunction "C_1") (pintype "input"))
      (node (ref "LED118") (pin "1") (pinfunction "C_1") (pintype "input"))
      (node (ref "LED119") (pin "1") (pinfunction "C_1") (pintype "input"))
      (node (ref "LED120") (pin "1") (pinfunction "C_1") (pintype "input"))
      (node (ref "LED121") (pin "1") (pinfunction "C_1") (pintype "input"))
      (node (ref "LED122") (pin "1") (pinfunction "C_1") (pintype "input"))
      (node (ref "LED123") (pin "1") (pinfunction "C_1") (pintype "input"))
      (node (ref "LED124") (pin "1") (pinfunction "C_1") (pintype "input"))
      (node (ref "LED125") (pin "1") (pinfunction "C_1") (pintype "input"))
      (node (ref "LED126") (pin "1") (pinfunction "C_1") (pintype "input"))
      (node (ref "LED127") (pin "1") (pinfunction "C_1") (pintype "input"))
      (node (ref "LED128") (pin "1") (pinfunction "C_1") (pintype "input"))
      (node (ref "U4") (pin "9") (pinfunction "COM7_9") (pintype "unspecified"))
    )
    (net (code "28") (name "/C8") (class "Default")
      (node (ref "D1") (pin "1") (pinfunction "A_1") (pintype "unspecified"))
      (node (ref "LED129") (pin "1") (pinfunction "C_1") (pintype "input"))
      (node (ref "LED130") (pin "1") (pinfunction "C_1") (pintype "input"))
      (node (ref "LED131") (pin "1") (pinfunction "C_1") (pintype "input"))
      (node (ref "LED132") (pin "1") (pinfunction "C_1") (pintype "input"))
      (node (ref "LED133") (pin "1") (pinfunction "C_1") (pintype "input"))
      (node (ref "LED134") (pin "1") (pinfunction "C_1") (pintype "input"))
      (node (ref "LED135") (pin "1") (pinfunction "C_1") (pintype "input"))
      (node (ref "LED136") (pin "1") (pinfunction "C_1") (pintype "input"))
      (node (ref "LED137") (pin "1") (pinfunction "C_1") (pintype "input"))
      (node (ref "LED138") (pin "1") (pinfunction "C_1") (pintype "input"))
      (node (ref "LED139") (pin "1") (pinfunction "C_1") (pintype "input"))
      (node (ref "LED140") (pin "1") (pinfunction "C_1") (pintype "input"))
      (node (ref "LED141") (pin "1") (pinfunction "C_1") (pintype "input"))
      (node (ref "LED142") (pin "1") (pinfunction "C_1") (pintype "input"))
      (node (ref "LED143") (pin "1") (pinfunction "C_1") (pintype "input"))
      (node (ref "LED144") (pin "1") (pinfunction "C_1") (pintype "input"))
      (node (ref "U5") (pin "2") (pinfunction "COM0/AD_2") (pintype "unspecified"))
    )
    (net (code "29") (name "/C9") (class "Default")
      (node (ref "LED145") (pin "1") (pinfunction "C_1") (pintype "input"))
      (node (ref "LED146") (pin "1") (pinfunction "C_1") (pintype "input"))
      (node (ref "LED147") (pin "1") (pinfunction "C_1") (pintype "input"))
      (node (ref "LED148") (pin "1") (pinfunction "C_1") (pintype "input"))
      (node (ref "LED149") (pin "1") (pinfunction "C_1") (pintype "input"))
      (node (ref "LED150") (pin "1") (pinfunction "C_1") (pintype "input"))
      (node (ref "LED151") (pin "1") (pinfunction "C_1") (pintype "input"))
      (node (ref "LED152") (pin "1") (pinfunction "C_1") (pintype "input"))
      (node (ref "LED153") (pin "1") (pinfunction "C_1") (pintype "input"))
      (node (ref "LED154") (pin "1") (pinfunction "C_1") (pintype "input"))
      (node (ref "LED155") (pin "1") (pinfunction "C_1") (pintype "input"))
      (node (ref "LED156") (pin "1") (pinfunction "C_1") (pintype "input"))
      (node (ref "LED157") (pin "1") (pinfunction "C_1") (pintype "input"))
      (node (ref "LED158") (pin "1") (pinfunction "C_1") (pintype "input"))
      (node (ref "LED159") (pin "1") (pinfunction "C_1") (pintype "input"))
      (node (ref "LED160") (pin "1") (pinfunction "C_1") (pintype "input"))
      (node (ref "U5") (pin "3") (pinfunction "COM1/KS0_3") (pintype "unspecified"))
    )
    (net (code "30") (name "/C10") (class "Default")
      (node (ref "LED161") (pin "1") (pinfunction "C_1") (pintype "input"))
      (node (ref "LED162") (pin "1") (pinfunction "C_1") (pintype "input"))
      (node (ref "LED163") (pin "1") (pinfunction "C_1") (pintype "input"))
      (node (ref "LED164") (pin "1") (pinfunction "C_1") (pintype "input"))
      (node (ref "LED165") (pin "1") (pinfunction "C_1") (pintype "input"))
      (node (ref "LED166") (pin "1") (pinfunction "C_1") (pintype "input"))
      (node (ref "LED167") (pin "1") (pinfunction "C_1") (pintype "input"))
      (node (ref "LED168") (pin "1") (pinfunction "C_1") (pintype "input"))
      (node (ref "LED169") (pin "1") (pinfunction "C_1") (pintype "input"))
      (node (ref "LED170") (pin "1") (pinfunction "C_1") (pintype "input"))
      (node (ref "LED171") (pin "1") (pinfunction "C_1") (pintype "input"))
      (node (ref "LED172") (pin "1") (pinfunction "C_1") (pintype "input"))
      (node (ref "LED173") (pin "1") (pinfunction "C_1") (pintype "input"))
      (node (ref "LED174") (pin "1") (pinfunction "C_1") (pintype "input"))
      (node (ref "LED175") (pin "1") (pinfunction "C_1") (pintype "input"))
      (node (ref "LED176") (pin "1") (pinfunction "C_1") (pintype "input"))
      (node (ref "U5") (pin "4") (pinfunction "COM2/KS1_4") (pintype "unspecified"))
    )
    (net (code "31") (name "/C11") (class "Default")
      (node (ref "LED177") (pin "1") (pinfunction "C_1") (pintype "input"))
      (node (ref "LED178") (pin "1") (pinfunction "C_1") (pintype "input"))
      (node (ref "LED179") (pin "1") (pinfunction "C_1") (pintype "input"))
      (node (ref "LED180") (pin "1") (pinfunction "C_1") (pintype "input"))
      (node (ref "LED181") (pin "1") (pinfunction "C_1") (pintype "input"))
      (node (ref "LED182") (pin "1") (pinfunction "C_1") (pintype "input"))
      (node (ref "LED183") (pin "1") (pinfunction "C_1") (pintype "input"))
      (node (ref "LED184") (pin "1") (pinfunction "C_1") (pintype "input"))
      (node (ref "LED185") (pin "1") (pinfunction "C_1") (pintype "input"))
      (node (ref "LED186") (pin "1") (pinfunction "C_1") (pintype "input"))
      (node (ref "LED187") (pin "1") (pinfunction "C_1") (pintype "input"))
      (node (ref "LED188") (pin "1") (pinfunction "C_1") (pintype "input"))
      (node (ref "LED189") (pin "1") (pinfunction "C_1") (pintype "input"))
      (node (ref "LED190") (pin "1") (pinfunction "C_1") (pintype "input"))
      (node (ref "LED191") (pin "1") (pinfunction "C_1") (pintype "input"))
      (node (ref "LED192") (pin "1") (pinfunction "C_1") (pintype "input"))
      (node (ref "U5") (pin "5") (pinfunction "COM3/KS2_5") (pintype "unspecified"))
    )
    (net (code "32") (name "/C12") (class "Default")
      (node (ref "LED194") (pin "1") (pinfunction "C_1") (pintype "input"))
      (node (ref "LED195") (pin "1") (pinfunction "C_1") (pintype "input"))
      (node (ref "LED196") (pin "1") (pinfunction "C_1") (pintype "input"))
      (node (ref "LED197") (pin "1") (pinfunction "C_1") (pintype "input"))
      (node (ref "LED198") (pin "1") (pinfunction "C_1") (pintype "input"))
      (node (ref "LED199") (pin "1") (pinfunction "C_1") (pintype "input"))
      (node (ref "LED200") (pin "1") (pinfunction "C_1") (pintype "input"))
      (node (ref "LED201") (pin "1") (pinfunction "C_1") (pintype "input"))
      (node (ref "LED202") (pin "1") (pinfunction "C_1") (pintype "input"))
      (node (ref "LED203") (pin "1") (pinfunction "C_1") (pintype "input"))
      (node (ref "LED204") (pin "1") (pinfunction "C_1") (pintype "input"))
      (node (ref "LED205") (pin "1") (pinfunction "C_1") (pintype "input"))
      (node (ref "LED206") (pin "1") (pinfunction "C_1") (pintype "input"))
      (node (ref "LED207") (pin "1") (pinfunction "C_1") (pintype "input"))
      (node (ref "U5") (pin "6") (pinfunction "COM4_6") (pintype "unspecified"))
    )
    (net (code "33") (name "/C13") (class "Default")
      (node (ref "LED211") (pin "1") (pinfunction "C_1") (pintype "input"))
      (node (ref "LED212") (pin "1") (pinfunction "C_1") (pintype "input"))
      (node (ref "LED213") (pin "1") (pinfunction "C_1") (pintype "input"))
      (node (ref "LED214") (pin "1") (pinfunction "C_1") (pintype "input"))
      (node (ref "LED215") (pin "1") (pinfunction "C_1") (pintype "input"))
      (node (ref "LED216") (pin "1") (pinfunction "C_1") (pintype "input"))
      (node (ref "LED217") (pin "1") (pinfunction "C_1") (pintype "input"))
      (node (ref "LED218") (pin "1") (pinfunction "C_1") (pintype "input"))
      (node (ref "LED219") (pin "1") (pinfunction "C_1") (pintype "input"))
      (node (ref "LED220") (pin "1") (pinfunction "C_1") (pintype "input"))
      (node (ref "LED221") (pin "1") (pinfunction "C_1") (pintype "input"))
      (node (ref "LED222") (pin "1") (pinfunction "C_1") (pintype "input"))
      (node (ref "U5") (pin "7") (pinfunction "COM5_7") (pintype "unspecified"))
    )
    (net (code "34") (name "/C14") (class "Default")
      (node (ref "LED228") (pin "1") (pinfunction "C_1") (pintype "input"))
      (node (ref "LED229") (pin "1") (pinfunction "C_1") (pintype "input"))
      (node (ref "LED230") (pin "1") (pinfunction "C_1") (pintype "input"))
      (node (ref "LED231") (pin "1") (pinfunction "C_1") (pintype "input"))
      (node (ref "LED232") (pin "1") (pinfunction "C_1") (pintype "input"))
      (node (ref "LED233") (pin "1") (pinfunction "C_1") (pintype "input"))
      (node (ref "LED234") (pin "1") (pinfunction "C_1") (pintype "input"))
      (node (ref "LED235") (pin "1") (pinfunction "C_1") (pintype "input"))
      (node (ref "LED236") (pin "1") (pinfunction "C_1") (pintype "input"))
      (node (ref "LED237") (pin "1") (pinfunction "C_1") (pintype "input"))
      (node (ref "U5") (pin "8") (pinfunction "COM6_8") (pintype "unspecified"))
    )
    (net (code "35") (name "/C15") (class "Default")
      (node (ref "LED245") (pin "1") (pinfunction "C_1") (pintype "input"))
      (node (ref "LED246") (pin "1") (pinfunction "C_1") (pintype "input"))
      (node (ref "LED247") (pin "1") (pinfunction "C_1") (pintype "input"))
      (node (ref "LED248") (pin "1") (pinfunction "C_1") (pintype "input"))
      (node (ref "LED249") (pin "1") (pinfunction "C_1") (pintype "input"))
      (node (ref "LED250") (pin "1") (pinfunction "C_1") (pintype "input"))
      (node (ref "LED251") (pin "1") (pinfunction "C_1") (pintype "input"))
      (node (ref "LED252") (pin "1") (pinfunction "C_1") (pintype "input"))
      (node (ref "U5") (pin "9") (pinfunction "COM7_9") (pintype "unspecified"))
    )
    (net (code "36") (name "/GPIO4") (class "Default")
      (node (ref "U3") (pin "12") (pinfunction "INT_12") (pintype "unspecified"))
      (node (ref "U6") (pin "8") (pinfunction "GPIO4_8") (pintype "input"))
    )
    (net (code "37") (name "/R0") (class "Default")
      (node (ref "LED113") (pin "2") (pinfunction "A_2") (pintype "input"))
      (node (ref "LED65") (pin "2") (pinfunction "A_2") (pintype "input"))
      (node (ref "LED81") (pin "2") (pinfunction "A_2") (pintype "input"))
      (node (ref "LED97") (pin "2") (pinfunction "A_2") (pintype "input"))
      (node (ref "U4") (pin "25") (pinfunction "ROW0/A2_25") (pintype "unspecified"))
    )
    (net (code "38") (name "/R1") (class "Default")
      (node (ref "LED114") (pin "2") (pinfunction "A_2") (pintype "input"))
      (node (ref "LED50") (pin "2") (pinfunction "A_2") (pintype "input"))
      (node (ref "LED66") (pin "2") (pinfunction "A_2") (pintype "input"))
      (node (ref "LED82") (pin "2") (pinfunction "A_2") (pintype "input"))
      (node (ref "LED98") (pin "2") (pinfunction "A_2") (pintype "input"))
      (node (ref "U4") (pin "24") (pinfunction "ROW1/A1_24") (pintype "unspecified"))
    )
    (net (code "39") (name "/R2") (class "Default")
      (node (ref "LED115") (pin "2") (pinfunction "A_2") (pintype "input"))
      (node (ref "LED35") (pin "2") (pinfunction "A_2") (pintype "input"))
      (node (ref "LED51") (pin "2") (pinfunction "A_2") (pintype "input"))
      (node (ref "LED67") (pin "2") (pinfunction "A_2") (pintype "input"))
      (node (ref "LED83") (pin "2") (pinfunction "A_2") (pintype "input"))
      (node (ref "LED99") (pin "2") (pinfunction "A_2") (pintype "input"))
      (node (ref "U4") (pin "23") (pinfunction "ROW2/A0_23") (pintype "unspecified"))
    )
    (net (code "40") (name "/R3") (class "Default")
      (node (ref "LED100") (pin "2") (pinfunction "A_2") (pintype "input"))
      (node (ref "LED116") (pin "2") (pinfunction "A_2") (pintype "input"))
      (node (ref "LED20") (pin "2") (pinfunction "A_2") (pintype "input"))
      (node (ref "LED36") (pin "2") (pinfunction "A_2") (pintype "input"))
      (node (ref "LED52") (pin "2") (pinfunction "A_2") (pintype "input"))
      (node (ref "LED68") (pin "2") (pinfunction "A_2") (pintype "input"))
      (node (ref "LED84") (pin "2") (pinfunction "A_2") (pintype "input"))
      (node (ref "U4") (pin "22") (pinfunction "ROW3/K1_22") (pintype "unspecified"))
    )
    (net (code "41") (name "/R4") (class "Default")
      (node (ref "LED101") (pin "2") (pinfunction "A_2") (pintype "input"))
      (node (ref "LED117") (pin "2") (pinfunction "A_2") (pintype "input"))
      (node (ref "LED21") (pin "2") (pinfunction "A_2") (pintype "input"))
      (node (ref "LED37") (pin "2") (pinfunction "A_2") (pintype "input"))
      (node (ref "LED5") (pin "2") (pinfunction "A_2") (pintype "input"))
      (node (ref "LED53") (pin "2") (pinfunction "A_2") (pintype "input"))
      (node (ref "LED69") (pin "2") (pinfunction "A_2") (pintype "input"))
      (node (ref "LED85") (pin "2") (pinfunction "A_2") (pintype "input"))
      (node (ref "U4") (pin "21") (pinfunction "ROW4/K2_21") (pintype "unspecified"))
    )
    (net (code "42") (name "/R5") (class "Default")
      (node (ref "LED102") (pin "2") (pinfunction "A_2") (pintype "input"))
      (node (ref "LED118") (pin "2") (pinfunction "A_2") (pintype "input"))
      (node (ref "LED22") (pin "2") (pinfunction "A_2") (pintype "input"))
      (node (ref "LED38") (pin "2") (pinfunction "A_2") (pintype "input"))
      (node (ref "LED54") (pin "2") (pinfunction "A_2") (pintype "input"))
      (node (ref "LED6") (pin "2") (pinfunction "A_2") (pintype "input"))
      (node (ref "LED70") (pin "2") (pinfunction "A_2") (pintype "input"))
      (node (ref "LED86") (pin "2") (pinfunction "A_2") (pintype "input"))
      (node (ref "U4") (pin "20") (pinfunction "ROW5/K3_20") (pintype "unspecified"))
    )
    (net (code "43") (name "/R6") (class "Default")
      (node (ref "LED103") (pin "2") (pinfunction "A_2") (pintype "input"))
      (node (ref "LED119") (pin "2") (pinfunction "A_2") (pintype "input"))
      (node (ref "LED23") (pin "2") (pinfunction "A_2") (pintype "input"))
      (node (ref "LED39") (pin "2") (pinfunction "A_2") (pintype "input"))
      (node (ref "LED55") (pin "2") (pinfunction "A_2") (pintype "input"))
      (node (ref "LED7") (pin "2") (pinfunction "A_2") (pintype "input"))
      (node (ref "LED71") (pin "2") (pinfunction "A_2") (pintype "input"))
      (node (ref "LED87") (pin "2") (pinfunction "A_2") (pintype "input"))
      (node (ref "U4") (pin "19") (pinfunction "ROW6/K4_19") (pintype "unspecified"))
    )
    (net (code "44") (name "/R7") (class "Default")
      (node (ref "LED104") (pin "2") (pinfunction "A_2") (pintype "input"))
      (node (ref "LED120") (pin "2") (pinfunction "A_2") (pintype "input"))
      (node (ref "LED24") (pin "2") (pinfunction "A_2") (pintype "input"))
      (node (ref "LED40") (pin "2") (pinfunction "A_2") (pintype "input"))
      (node (ref "LED56") (pin "2") (pinfunction "A_2") (pintype "input"))
      (node (ref "LED72") (pin "2") (pinfunction "A_2") (pintype "input"))
      (node (ref "LED8") (pin "2") (pinfunction "A_2") (pintype "input"))
      (node (ref "LED88") (pin "2") (pinfunction "A_2") (pintype "input"))
      (node (ref "U4") (pin "18") (pinfunction "ROW7/K5_18") (pintype "unspecified"))
    )
    (net (code "45") (name "/R8") (class "Default")
      (node (ref "LED105") (pin "2") (pinfunction "A_2") (pintype "input"))
      (node (ref "LED121") (pin "2") (pinfunction "A_2") (pintype "input"))
      (node (ref "LED25") (pin "2") (pinfunction "A_2") (pintype "input"))
      (node (ref "LED41") (pin "2") (pinfunction "A_2") (pintype "input"))
      (node (ref "LED57") (pin "2") (pinfunction "A_2") (pintype "input"))
      (node (ref "LED73") (pin "2") (pinfunction "A_2") (pintype "input"))
      (node (ref "LED89") (pin "2") (pinfunction "A_2") (pintype "input"))
      (node (ref "LED9") (pin "2") (pinfunction "A_2") (pintype "input"))
      (node (ref "U4") (pin "17") (pinfunction "ROW8/K6_17") (pintype "unspecified"))
    )
    (net (code "46") (name "/R9") (class "Default")
      (node (ref "LED10") (pin "2") (pinfunction "A_2") (pintype "input"))
      (node (ref "LED106") (pin "2") (pinfunction "A_2") (pintype "input"))
      (node (ref "LED122") (pin "2") (pinfunction "A_2") (pintype "input"))
      (node (ref "LED26") (pin "2") (pinfunction "A_2") (pintype "input"))
      (node (ref "LED42") (pin "2") (pinfunction "A_2") (pintype "input"))
      (node (ref "LED58") (pin "2") (pinfunction "A_2") (pintype "input"))
      (node (ref "LED74") (pin "2") (pinfunction "A_2") (pintype "input"))
      (node (ref "LED90") (pin "2") (pinfunction "A_2") (pintype "input"))
      (node (ref "U4") (pin "16") (pinfunction "ROW9/K7_16") (pintype "unspecified"))
    )
    (net (code "47") (name "/R10") (class "Default")
      (node (ref "LED107") (pin "2") (pinfunction "A_2") (pintype "input"))
      (node (ref "LED11") (pin "2") (pinfunction "A_2") (pintype "input"))
      (node (ref "LED123") (pin "2") (pinfunction "A_2") (pintype "input"))
      (node (ref "LED27") (pin "2") (pinfunction "A_2") (pintype "input"))
      (node (ref "LED43") (pin "2") (pinfunction "A_2") (pintype "input"))
      (node (ref "LED59") (pin "2") (pinfunction "A_2") (pintype "input"))
      (node (ref "LED75") (pin "2") (pinfunction "A_2") (pintype "input"))
      (node (ref "LED91") (pin "2") (pinfunction "A_2") (pintype "input"))
      (node (ref "U4") (pin "15") (pinfunction "ROW10/K8_15") (pintype "unspecified"))
    )
    (net (code "48") (name "/R11") (class "Default")
      (node (ref "LED108") (pin "2") (pinfunction "A_2") (pintype "input"))
      (node (ref "LED12") (pin "2") (pinfunction "A_2") (pintype "input"))
      (node (ref "LED124") (pin "2") (pinfunction "A_2") (pintype "input"))
      (node (ref "LED28") (pin "2") (pinfunction "A_2") (pintype "input"))
      (node (ref "LED44") (pin "2") (pinfunction "A_2") (pintype "input"))
      (node (ref "LED60") (pin "2") (pinfunction "A_2") (pintype "input"))
      (node (ref "LED76") (pin "2") (pinfunction "A_2") (pintype "input"))
      (node (ref "LED92") (pin "2") (pinfunction "A_2") (pintype "input"))
      (node (ref "U4") (pin "14") (pinfunction "ROW11/K9_14") (pintype "unspecified"))
    )
    (net (code "49") (name "/R12") (class "Default")
      (node (ref "LED109") (pin "2") (pinfunction "A_2") (pintype "input"))
      (node (ref "LED125") (pin "2") (pinfunction "A_2") (pintype "input"))
      (node (ref "LED29") (pin "2") (pinfunction "A_2") (pintype "input"))
      (node (ref "LED45") (pin "2") (pinfunction "A_2") (pintype "input"))
      (node (ref "LED61") (pin "2") (pinfunction "A_2") (pintype "input"))
      (node (ref "LED77") (pin "2") (pinfunction "A_2") (pintype "input"))
      (node (ref "LED93") (pin "2") (pinfunction "A_2") (pintype "input"))
      (node (ref "U4") (pin "13") (pinfunction "ROW12/K10_13") (pintype "unspecified"))
    )
    (net (code "50") (name "/R13") (class "Default")
      (node (ref "LED110") (pin "2") (pinfunction "A_2") (pintype "input"))
      (node (ref "LED126") (pin "2") (pinfunction "A_2") (pintype "input"))
      (node (ref "LED46") (pin "2") (pinfunction "A_2") (pintype "input"))
      (node (ref "LED62") (pin "2") (pinfunction "A_2") (pintype "input"))
      (node (ref "LED78") (pin "2") (pinfunction "A_2") (pintype "input"))
      (node (ref "LED94") (pin "2") (pinfunction "A_2") (pintype "input"))
      (node (ref "U4") (pin "12") (pinfunction "ROW13/K11_12") (pintype "unspecified"))
    )
    (net (code "51") (name "/R14") (class "Default")
      (node (ref "LED111") (pin "2") (pinfunction "A_2") (pintype "input"))
      (node (ref "LED127") (pin "2") (pinfunction "A_2") (pintype "input"))
      (node (ref "LED63") (pin "2") (pinfunction "A_2") (pintype "input"))
      (node (ref "LED79") (pin "2") (pinfunction "A_2") (pintype "input"))
      (node (ref "LED95") (pin "2") (pinfunction "A_2") (pintype "input"))
      (node (ref "U4") (pin "11") (pinfunction "ROW14/K12_11") (pintype "unspecified"))
    )
    (net (code "52") (name "/R15") (class "Default")
      (node (ref "LED112") (pin "2") (pinfunction "A_2") (pintype "input"))
      (node (ref "LED128") (pin "2") (pinfunction "A_2") (pintype "input"))
      (node (ref "LED80") (pin "2") (pinfunction "A_2") (pintype "input"))
      (node (ref "LED96") (pin "2") (pinfunction "A_2") (pintype "input"))
      (node (ref "U4") (pin "10") (pinfunction "ROW15/K13/INT_10") (pintype "unspecified"))
    )
    (net (code "53") (name "/SCK") (class "Default")
      (node (ref "R2") (pin "1") (pinfunction "1_1") (pintype "input"))
      (node (ref "U3") (pin "23") (pinfunction "SCL_23") (pintype "unspecified"))
      (node (ref "U4") (pin "26") (pinfunction "SCL_26") (pintype "unspecified"))
      (node (ref "U5") (pin "26") (pinfunction "SCL_26") (pintype "unspecified"))
      (node (ref "U6") (pin "13") (pinfunction "GPIO9_13") (pintype "input"))
    )
    (net (code "54") (name "/SDA") (class "Default")
      (node (ref "R1") (pin "1") (pinfunction "1_1") (pintype "input"))
      (node (ref "U3") (pin "24") (pinfunction "SDA_24") (pintype "unspecified"))
      (node (ref "U4") (pin "27") (pinfunction "SDA_27") (pintype "unspecified"))
      (node (ref "U5") (pin "27") (pinfunction "SDA_27") (pintype "unspecified"))
      (node (ref "U6") (pin "12") (pinfunction "GPIO8_12") (pintype "input"))
    )
    (net (code "55") (name "GND") (class "Default")
      (node (ref "C1") (pin "2") (pinfunction "2_2") (pintype "input"))
      (node (ref "C2") (pin "1") (pinfunction "1_1") (pintype "input"))
      (node (ref "C3") (pin "2") (pinfunction "2_2") (pintype "input"))
      (node (ref "C4") (pin "2") (pinfunction "2_2") (pintype "input"))
      (node (ref "C5") (pin "2") (pinfunction "2_2") (pintype "input"))
      (node (ref "C6") (pin "2") (pinfunction "2_2") (pintype "input"))
      (node (ref "U3") (pin "18") (pinfunction "GND_18") (pintype "unspecified"))
      (node (ref "U3") (pin "9") (pinfunction "AD0_9") (pintype "unspecified"))
      (node (ref "U4") (pin "1") (pinfunction "VSS_1") (pintype "unspecified"))
      (node (ref "U5") (pin "1") (pinfunction "VSS_1") (pintype "unspecified"))
      (node (ref "U6") (pin "19") (pinfunction "GND_19") (pintype "input"))
    )
    (net (code "56") (name "Net-(D1-K)") (class "Default")
      (node (ref "D1") (pin "2") (pinfunction "K_2") (pintype "unspecified"))
      (node (ref "R3") (pin "2") (pinfunction "2_2") (pintype "input"))
    )
    (net (code "57") (name "Net-(U3-CPOUT)") (class "Default")
      (node (ref "C1") (pin "1") (pinfunction "1_1") (pintype "input"))
      (node (ref "U3") (pin "20") (pinfunction "CPOUT_20") (pintype "unspecified"))
    )
    (net (code "58") (name "Net-(U3-REGOUT)") (class "Default")
      (node (ref "C2") (pin "2") (pinfunction "2_2") (pintype "input"))
      (node (ref "U3") (pin "10") (pinfunction "REGOUT_10") (pintype "unspecified"))
    )
    (net (code "59") (name "unconnected-(U3-AUX_CL-Pad7)") (class "Default")
      (node (ref "U3") (pin "7") (pinfunction "AUX_CL_7") (pintype "unspecified+no_connect"))
    )
    (net (code "60") (name "unconnected-(U3-AUX_DA-Pad6)") (class "Default")
      (node (ref "U3") (pin "6") (pinfunction "AUX_DA_6") (pintype "unspecified+no_connect"))
    )
    (net (code "61") (name "unconnected-(U3-CLKIN-Pad1)") (class "Default")
      (node (ref "U3") (pin "1") (pinfunction "CLKIN_1") (pintype "unspecified+no_connect"))
    )
    (net (code "62") (name "unconnected-(U3-FSYNC-Pad11)") (class "Default")
      (node (ref "U3") (pin "11") (pinfunction "FSYNC_11") (pintype "unspecified+no_connect"))
    )
    (net (code "63") (name "unconnected-(U3-NC-Pad2)") (class "Default")
      (node (ref "U3") (pin "2") (pinfunction "NC_2") (pintype "unspecified+no_connect"))
    )
    (net (code "64") (name "unconnected-(U3-NC-Pad3)") (class "Default")
      (node (ref "U3") (pin "3") (pinfunction "NC_3") (pintype "unspecified+no_connect"))
    )
    (net (code "65") (name "unconnected-(U3-NC-Pad4)") (class "Default")
      (node (ref "U3") (pin "4") (pinfunction "NC_4") (pintype "unspecified+no_connect"))
    )
    (net (code "66") (name "unconnected-(U3-NC-Pad5)") (class "Default")
      (node (ref "U3") (pin "5") (pinfunction "NC_5") (pintype "unspecified+no_connect"))
    )
    (net (code "67") (name "unconnected-(U3-NC-Pad14)") (class "Default")
      (node (ref "U3") (pin "14") (pinfunction "NC_14") (pintype "unspecified+no_connect"))
    )
    (net (code "68") (name "unconnected-(U3-NC-Pad15)") (class "Default")
      (node (ref "U3") (pin "15") (pinfunction "NC_15") (pintype "unspecified+no_connect"))
    )
    (net (code "69") (name "unconnected-(U3-NC-Pad16)") (class "Default")
      (node (ref "U3") (pin "16") (pinfunction "NC_16") (pintype "unspecified+no_connect"))
    )
    (net (code "70") (name "unconnected-(U3-NC-Pad17)") (class "Default")
      (node (ref "U3") (pin "17") (pinfunction "NC_17") (pintype "unspecified+no_connect"))
    )
    (net (code "71") (name "unconnected-(U3-RESV-Pad19)") (class "Default")
      (node (ref "U3") (pin "19") (pinfunction "RESV_19") (pintype "unspecified+no_connect"))
    )
    (net (code "72") (name "unconnected-(U3-RESV-Pad21)") (class "Default")
      (node (ref "U3") (pin "21") (pinfunction "RESV_21") (pintype "unspecified+no_connect"))
    )
    (net (code "73") (name "unconnected-(U3-RESV-Pad22)") (class "Default")
      (node (ref "U3") (pin "22") (pinfunction "RESV_22") (pintype "unspecified+no_connect"))
    )
    (net (code "74") (name "unconnected-(U6-5V-Pad20)") (class "Default")
      (node (ref "U6") (pin "20") (pinfunction "5V_20") (pintype "input+no_connect"))
    )
    (net (code "75") (name "unconnected-(U6-GPIO1-Pad5)") (class "Default")
      (node (ref "U6") (pin "5") (pinfunction "GPIO1_5") (pintype "input+no_connect"))
    )
    (net (code "76") (name "unconnected-(U6-GPIO2-Pad6)") (class "Default")
      (node (ref "U6") (pin "6") (pinfunction "GPIO2_6") (pintype "input+no_connect"))
    )
    (net (code "77") (name "unconnected-(U6-GPIO3-Pad7)") (class "Default")
      (node (ref "U6") (pin "7") (pinfunction "GPIO3_7") (pintype "input+no_connect"))
    )
    (net (code "78") (name "unconnected-(U6-GPIO5-Pad9)") (class "Default")
      (node (ref "U6") (pin "9") (pinfunction "GPIO5_9") (pintype "input+no_connect"))
    )
    (net (code "79") (name "unconnected-(U6-GPIO6-Pad10)") (class "Default")
      (node (ref "U6") (pin "10") (pinfunction "GPIO6_10") (pintype "input+no_connect"))
    )
    (net (code "80") (name "unconnected-(U6-GPIO7-Pad11)") (class "Default")
      (node (ref "U6") (pin "11") (pinfunction "GPIO7_11") (pintype "input+no_connect"))
    )
    (net (code "81") (name "unconnected-(U6-GPIO10-Pad14)") (class "Default")
      (node (ref "U6") (pin "14") (pinfunction "GPIO10_14") (pintype "input+no_connect"))
    )
    (net (code "82") (name "unconnected-(U6-GPIO11-Pad15)") (class "Default")
      (node (ref "U6") (pin "15") (pinfunction "GPIO11_15") (pintype "input+no_connect"))
    )
    (net (code "83") (name "unconnected-(U6-GPIO12-Pad16)") (class "Default")
      (node (ref "U6") (pin "16") (pinfunction "GPIO12_16") (pintype "input+no_connect"))
    )
    (net (code "84") (name "unconnected-(U6-GPIO13-Pad17)") (class "Default")
      (node (ref "U6") (pin "17") (pinfunction "GPIO13_17") (pintype "input+no_connect"))
    )
    (net (code "85") (name "unconnected-(U6-RX-Pad4)") (class "Default")
      (node (ref "U6") (pin "4") (pinfunction "RX_4") (pintype "input+no_connect"))
    )
    (net (code "86") (name "unconnected-(U6-TX-Pad3)") (class "Default")
      (node (ref "U6") (pin "3") (pinfunction "TX_3") (pintype "input+no_connect"))
    )
  )
)
